# SWITCHING.net
KiCad netlist of a schematic drawn in Altium Designer
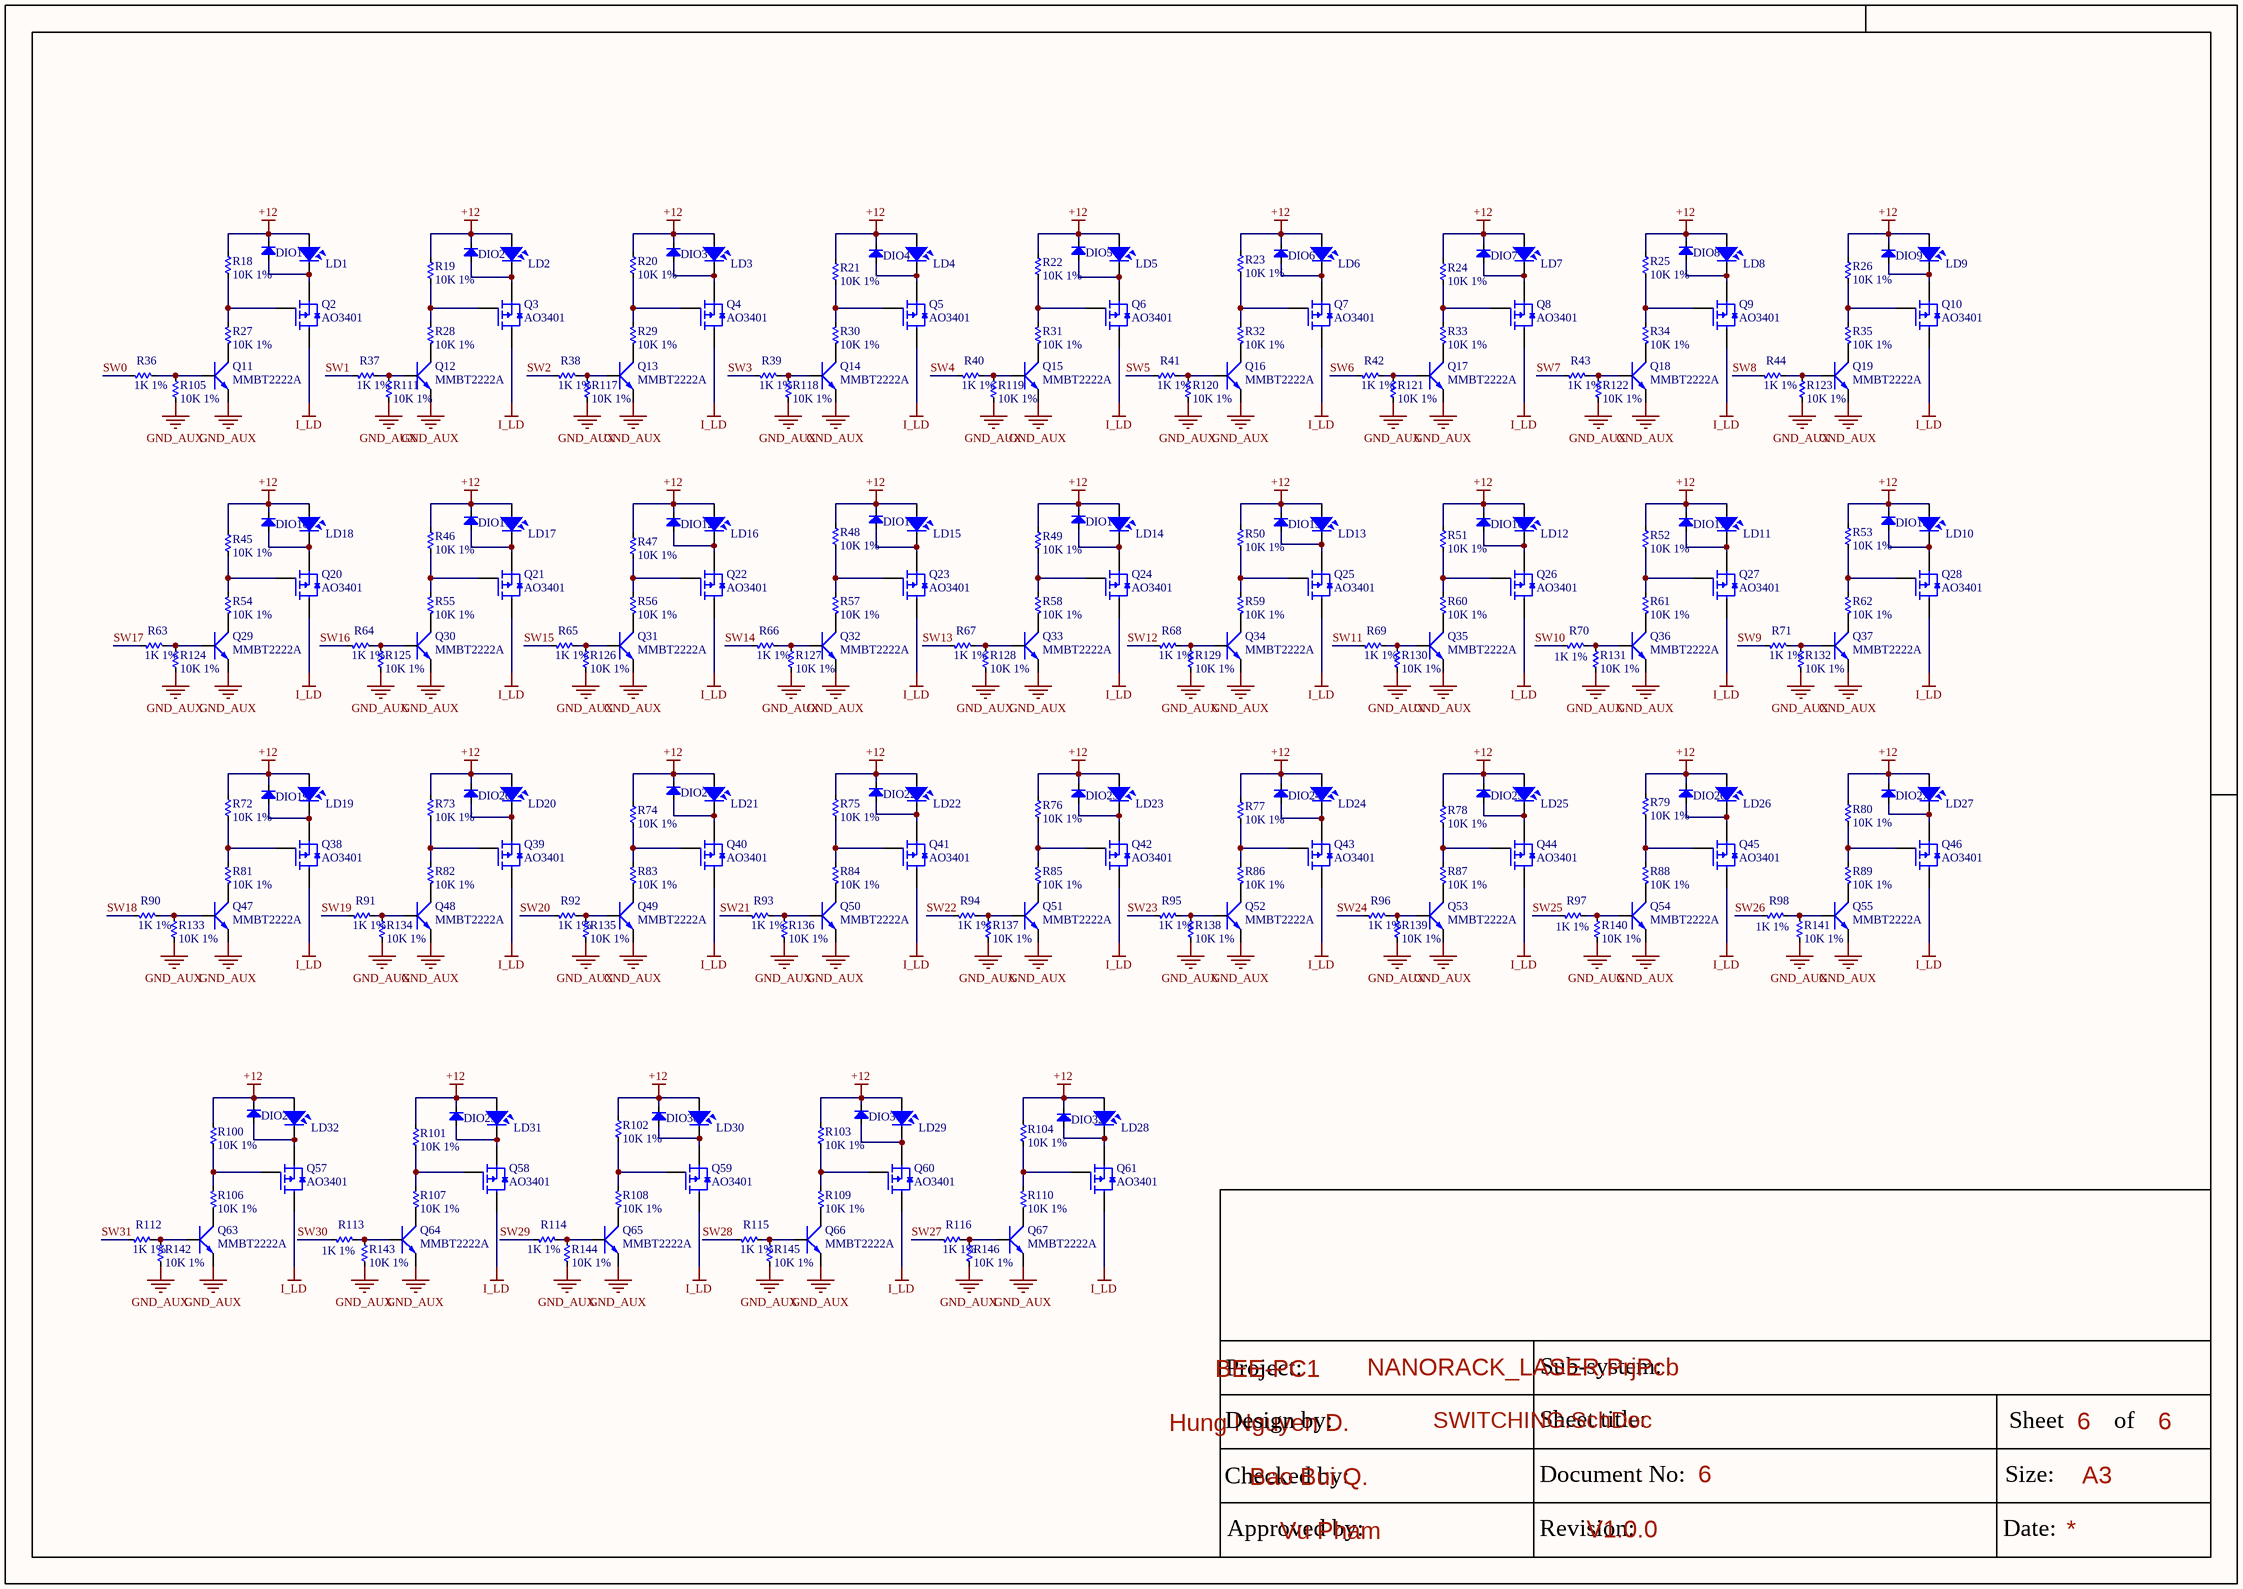
[diagram p0: SWITCHING.SchDoc]

(export (version "E")
  (design (tool "Eeschema 10.0.6"))
  (components
    (comp (ref "DIO1")
      (value "Diode SMD")
      (footprint "SOD23")
      (description "Default Diode")
      (fields (field (name "PUBLISHER") "Altium Limited"))
      (libsource (lib "Library") (part "Diode SMD"))
    )
    (comp (ref "DIO2")
      (value "Diode SMD")
      (footprint "SOD23")
      (description "Default Diode")
      (fields (field (name "PUBLISHER") "Altium Limited"))
      (libsource (lib "Library") (part "Diode SMD"))
    )
    (comp (ref "DIO3")
      (value "Diode SMD")
      (footprint "SOD23")
      (description "Default Diode")
      (fields (field (name "PUBLISHER") "Altium Limited"))
      (libsource (lib "Library") (part "Diode SMD"))
    )
    (comp (ref "DIO4")
      (value "Diode SMD")
      (footprint "SOD23")
      (description "Default Diode")
      (fields (field (name "PUBLISHER") "Altium Limited"))
      (libsource (lib "Library") (part "Diode SMD"))
    )
    (comp (ref "DIO5")
      (value "Diode SMD")
      (footprint "SOD23")
      (description "Default Diode")
      (fields (field (name "PUBLISHER") "Altium Limited"))
      (libsource (lib "Library") (part "Diode SMD"))
    )
    (comp (ref "DIO6")
      (value "Diode SMD")
      (footprint "SOD23")
      (description "Default Diode")
      (fields (field (name "PUBLISHER") "Altium Limited"))
      (libsource (lib "Library") (part "Diode SMD"))
    )
    (comp (ref "DIO7")
      (value "Diode SMD")
      (footprint "SOD23")
      (description "Default Diode")
      (fields (field (name "PUBLISHER") "Altium Limited"))
      (libsource (lib "Library") (part "Diode SMD"))
    )
    (comp (ref "DIO8")
      (value "Diode SMD")
      (footprint "SOD23")
      (description "Default Diode")
      (fields (field (name "PUBLISHER") "Altium Limited"))
      (libsource (lib "Library") (part "Diode SMD"))
    )
    (comp (ref "DIO9")
      (value "Diode SMD")
      (footprint "SOD23")
      (description "Default Diode")
      (fields (field (name "PUBLISHER") "Altium Limited"))
      (libsource (lib "Library") (part "Diode SMD"))
    )
    (comp (ref "DIO10")
      (value "Diode SMD")
      (footprint "SOD23")
      (description "Default Diode")
      (fields (field (name "PUBLISHER") "Altium Limited"))
      (libsource (lib "Library") (part "Diode SMD"))
    )
    (comp (ref "DIO11")
      (value "Diode SMD")
      (footprint "SOD23")
      (description "Default Diode")
      (fields (field (name "PUBLISHER") "Altium Limited"))
      (libsource (lib "Library") (part "Diode SMD"))
    )
    (comp (ref "DIO12")
      (value "Diode SMD")
      (footprint "SOD23")
      (description "Default Diode")
      (fields (field (name "PUBLISHER") "Altium Limited"))
      (libsource (lib "Library") (part "Diode SMD"))
    )
    (comp (ref "DIO13")
      (value "Diode SMD")
      (footprint "SOD23")
      (description "Default Diode")
      (fields (field (name "PUBLISHER") "Altium Limited"))
      (libsource (lib "Library") (part "Diode SMD"))
    )
    (comp (ref "DIO14")
      (value "Diode SMD")
      (footprint "SOD23")
      (description "Default Diode")
      (fields (field (name "PUBLISHER") "Altium Limited"))
      (libsource (lib "Library") (part "Diode SMD"))
    )
    (comp (ref "DIO15")
      (value "Diode SMD")
      (footprint "SOD23")
      (description "Default Diode")
      (fields (field (name "PUBLISHER") "Altium Limited"))
      (libsource (lib "Library") (part "Diode SMD"))
    )
    (comp (ref "DIO16")
      (value "Diode SMD")
      (footprint "SOD23")
      (description "Default Diode")
      (fields (field (name "PUBLISHER") "Altium Limited"))
      (libsource (lib "Library") (part "Diode SMD"))
    )
    (comp (ref "DIO17")
      (value "Diode SMD")
      (footprint "SOD23")
      (description "Default Diode")
      (fields (field (name "PUBLISHER") "Altium Limited"))
      (libsource (lib "Library") (part "Diode SMD"))
    )
    (comp (ref "DIO18")
      (value "Diode SMD")
      (footprint "SOD23")
      (description "Default Diode")
      (fields (field (name "PUBLISHER") "Altium Limited"))
      (libsource (lib "Library") (part "Diode SMD"))
    )
    (comp (ref "DIO19")
      (value "Diode SMD")
      (footprint "SOD23")
      (description "Default Diode")
      (fields (field (name "PUBLISHER") "Altium Limited"))
      (libsource (lib "Library") (part "Diode SMD"))
    )
    (comp (ref "DIO20")
      (value "Diode SMD")
      (footprint "SOD23")
      (description "Default Diode")
      (fields (field (name "PUBLISHER") "Altium Limited"))
      (libsource (lib "Library") (part "Diode SMD"))
    )
    (comp (ref "DIO21")
      (value "Diode SMD")
      (footprint "SOD23")
      (description "Default Diode")
      (fields (field (name "PUBLISHER") "Altium Limited"))
      (libsource (lib "Library") (part "Diode SMD"))
    )
    (comp (ref "DIO22")
      (value "Diode SMD")
      (footprint "SOD23")
      (description "Default Diode")
      (fields (field (name "PUBLISHER") "Altium Limited"))
      (libsource (lib "Library") (part "Diode SMD"))
    )
    (comp (ref "DIO23")
      (value "Diode SMD")
      (footprint "SOD23")
      (description "Default Diode")
      (fields (field (name "PUBLISHER") "Altium Limited"))
      (libsource (lib "Library") (part "Diode SMD"))
    )
    (comp (ref "DIO24")
      (value "Diode SMD")
      (footprint "SOD23")
      (description "Default Diode")
      (fields (field (name "PUBLISHER") "Altium Limited"))
      (libsource (lib "Library") (part "Diode SMD"))
    )
    (comp (ref "DIO25")
      (value "Diode SMD")
      (footprint "SOD23")
      (description "Default Diode")
      (fields (field (name "PUBLISHER") "Altium Limited"))
      (libsource (lib "Library") (part "Diode SMD"))
    )
    (comp (ref "DIO26")
      (value "Diode SMD")
      (footprint "SOD23")
      (description "Default Diode")
      (fields (field (name "PUBLISHER") "Altium Limited"))
      (libsource (lib "Library") (part "Diode SMD"))
    )
    (comp (ref "DIO27")
      (value "Diode SMD")
      (footprint "SOD23")
      (description "Default Diode")
      (fields (field (name "PUBLISHER") "Altium Limited"))
      (libsource (lib "Library") (part "Diode SMD"))
    )
    (comp (ref "DIO28")
      (value "Diode SMD")
      (footprint "SOD23")
      (description "Default Diode")
      (fields (field (name "PUBLISHER") "Altium Limited"))
      (libsource (lib "Library") (part "Diode SMD"))
    )
    (comp (ref "DIO29")
      (value "Diode SMD")
      (footprint "SOD23")
      (description "Default Diode")
      (fields (field (name "PUBLISHER") "Altium Limited"))
      (libsource (lib "Library") (part "Diode SMD"))
    )
    (comp (ref "DIO30")
      (value "Diode SMD")
      (footprint "SOD23")
      (description "Default Diode")
      (fields (field (name "PUBLISHER") "Altium Limited"))
      (libsource (lib "Library") (part "Diode SMD"))
    )
    (comp (ref "DIO31")
      (value "Diode SMD")
      (footprint "SOD23")
      (description "Default Diode")
      (fields (field (name "PUBLISHER") "Altium Limited"))
      (libsource (lib "Library") (part "Diode SMD"))
    )
    (comp (ref "DIO32")
      (value "Diode SMD")
      (footprint "SOD23")
      (description "Default Diode")
      (fields (field (name "PUBLISHER") "Altium Limited"))
      (libsource (lib "Library") (part "Diode SMD"))
    )
    (comp (ref "LD1") (value "LaserDiode") (footprint "LASER") (libsource (lib "Library") (part "LD")))
    (comp (ref "LD2") (value "LaserDiode") (footprint "LASER") (libsource (lib "Library") (part "LD")))
    (comp (ref "LD3") (value "LaserDiode") (footprint "LASER") (libsource (lib "Library") (part "LD")))
    (comp (ref "LD4") (value "LaserDiode") (footprint "LASER") (libsource (lib "Library") (part "LD")))
    (comp (ref "LD5") (value "LaserDiode") (footprint "LASER") (libsource (lib "Library") (part "LD")))
    (comp (ref "LD6") (value "LaserDiode") (footprint "LASER") (libsource (lib "Library") (part "LD")))
    (comp (ref "LD7") (value "LaserDiode") (footprint "LASER") (libsource (lib "Library") (part "LD")))
    (comp (ref "LD8") (value "LaserDiode") (footprint "LASER") (libsource (lib "Library") (part "LD")))
    (comp (ref "LD9") (value "LaserDiode") (footprint "LASER") (libsource (lib "Library") (part "LD")))
    (comp (ref "LD10") (value "LaserDiode") (footprint "LASER") (libsource (lib "Library") (part "LD")))
    (comp (ref "LD11") (value "LaserDiode") (footprint "LASER") (libsource (lib "Library") (part "LD")))
    (comp (ref "LD12") (value "LaserDiode") (footprint "LASER") (libsource (lib "Library") (part "LD")))
    (comp (ref "LD13") (value "LaserDiode") (footprint "LASER") (libsource (lib "Library") (part "LD")))
    (comp (ref "LD14") (value "LaserDiode") (footprint "LASER") (libsource (lib "Library") (part "LD")))
    (comp (ref "LD15") (value "LaserDiode") (footprint "LASER") (libsource (lib "Library") (part "LD")))
    (comp (ref "LD16") (value "LaserDiode") (footprint "LASER") (libsource (lib "Library") (part "LD")))
    (comp (ref "LD17") (value "LaserDiode") (footprint "LASER") (libsource (lib "Library") (part "LD")))
    (comp (ref "LD18") (value "LaserDiode") (footprint "LASER") (libsource (lib "Library") (part "LD")))
    (comp (ref "LD19") (value "LaserDiode") (footprint "LASER") (libsource (lib "Library") (part "LD")))
    (comp (ref "LD20") (value "LaserDiode") (footprint "LASER") (libsource (lib "Library") (part "LD")))
    (comp (ref "LD21") (value "LaserDiode") (footprint "LASER") (libsource (lib "Library") (part "LD")))
    (comp (ref "LD22") (value "LaserDiode") (footprint "LASER") (libsource (lib "Library") (part "LD")))
    (comp (ref "LD23") (value "LaserDiode") (footprint "LASER") (libsource (lib "Library") (part "LD")))
    (comp (ref "LD24") (value "LaserDiode") (footprint "LASER") (libsource (lib "Library") (part "LD")))
    (comp (ref "LD25") (value "LaserDiode") (footprint "LASER") (libsource (lib "Library") (part "LD")))
    (comp (ref "LD26") (value "LaserDiode") (footprint "LASER") (libsource (lib "Library") (part "LD")))
    (comp (ref "LD27") (value "LaserDiode") (footprint "LASER") (libsource (lib "Library") (part "LD")))
    (comp (ref "LD28") (value "LaserDiode") (footprint "LASER") (libsource (lib "Library") (part "LD")))
    (comp (ref "LD29") (value "LaserDiode") (footprint "LASER") (libsource (lib "Library") (part "LD")))
    (comp (ref "LD30") (value "LaserDiode") (footprint "LASER") (libsource (lib "Library") (part "LD")))
    (comp (ref "LD31") (value "LaserDiode") (footprint "LASER") (libsource (lib "Library") (part "LD")))
    (comp (ref "LD32") (value "LaserDiode") (footprint "LASER") (libsource (lib "Library") (part "LD")))
    (comp (ref "Q2") (value "AO3401") (footprint "SOT23-123") (libsource (lib "Library") (part "FET-P")))
    (comp (ref "Q3") (value "AO3401") (footprint "SOT23-123") (libsource (lib "Library") (part "FET-P")))
    (comp (ref "Q4") (value "AO3401") (footprint "SOT23-123") (libsource (lib "Library") (part "FET-P")))
    (comp (ref "Q5") (value "AO3401") (footprint "SOT23-123") (libsource (lib "Library") (part "FET-P")))
    (comp (ref "Q6") (value "AO3401") (footprint "SOT23-123") (libsource (lib "Library") (part "FET-P")))
    (comp (ref "Q7") (value "AO3401") (footprint "SOT23-123") (libsource (lib "Library") (part "FET-P")))
    (comp (ref "Q8") (value "AO3401") (footprint "SOT23-123") (libsource (lib "Library") (part "FET-P")))
    (comp (ref "Q9") (value "AO3401") (footprint "SOT23-123") (libsource (lib "Library") (part "FET-P")))
    (comp (ref "Q10") (value "AO3401") (footprint "SOT23-123") (libsource (lib "Library") (part "FET-P")))
    (comp (ref "Q11")
      (value "MMBT2222A")
      (footprint "SOT23-132")
      (description "SOT23-3")
      (libsource (lib "Library") (part "2SC1815"))
    )
    (comp (ref "Q12")
      (value "MMBT2222A")
      (footprint "SOT23-132")
      (description "SOT23-3")
      (libsource (lib "Library") (part "2SC1815"))
    )
    (comp (ref "Q13")
      (value "MMBT2222A")
      (footprint "SOT23-132")
      (description "SOT23-3")
      (libsource (lib "Library") (part "2SC1815"))
    )
    (comp (ref "Q14")
      (value "MMBT2222A")
      (footprint "SOT23-132")
      (description "SOT23-3")
      (libsource (lib "Library") (part "2SC1815"))
    )
    (comp (ref "Q15")
      (value "MMBT2222A")
      (footprint "SOT23-132")
      (description "SOT23-3")
      (libsource (lib "Library") (part "2SC1815"))
    )
    (comp (ref "Q16")
      (value "MMBT2222A")
      (footprint "SOT23-132")
      (description "SOT23-3")
      (libsource (lib "Library") (part "2SC1815"))
    )
    (comp (ref "Q17")
      (value "MMBT2222A")
      (footprint "SOT23-132")
      (description "SOT23-3")
      (libsource (lib "Library") (part "2SC1815"))
    )
    (comp (ref "Q18")
      (value "MMBT2222A")
      (footprint "SOT23-132")
      (description "SOT23-3")
      (libsource (lib "Library") (part "2SC1815"))
    )
    (comp (ref "Q19")
      (value "MMBT2222A")
      (footprint "SOT23-132")
      (description "SOT23-3")
      (libsource (lib "Library") (part "2SC1815"))
    )
    (comp (ref "Q20") (value "AO3401") (footprint "SOT23-123") (libsource (lib "Library") (part "FET-P")))
    (comp (ref "Q21") (value "AO3401") (footprint "SOT23-123") (libsource (lib "Library") (part "FET-P")))
    (comp (ref "Q22") (value "AO3401") (footprint "SOT23-123") (libsource (lib "Library") (part "FET-P")))
    (comp (ref "Q23") (value "AO3401") (footprint "SOT23-123") (libsource (lib "Library") (part "FET-P")))
    (comp (ref "Q24") (value "AO3401") (footprint "SOT23-123") (libsource (lib "Library") (part "FET-P")))
    (comp (ref "Q25") (value "AO3401") (footprint "SOT23-123") (libsource (lib "Library") (part "FET-P")))
    (comp (ref "Q26") (value "AO3401") (footprint "SOT23-123") (libsource (lib "Library") (part "FET-P")))
    (comp (ref "Q27") (value "AO3401") (footprint "SOT23-123") (libsource (lib "Library") (part "FET-P")))
    (comp (ref "Q28") (value "AO3401") (footprint "SOT23-123") (libsource (lib "Library") (part "FET-P")))
    (comp (ref "Q29")
      (value "MMBT2222A")
      (footprint "SOT23-132")
      (description "SOT23-3")
      (libsource (lib "Library") (part "2SC1815"))
    )
    (comp (ref "Q30")
      (value "MMBT2222A")
      (footprint "SOT23-132")
      (description "SOT23-3")
      (libsource (lib "Library") (part "2SC1815"))
    )
    (comp (ref "Q31")
      (value "MMBT2222A")
      (footprint "SOT23-132")
      (description "SOT23-3")
      (libsource (lib "Library") (part "2SC1815"))
    )
    (comp (ref "Q32")
      (value "MMBT2222A")
      (footprint "SOT23-132")
      (description "SOT23-3")
      (libsource (lib "Library") (part "2SC1815"))
    )
    (comp (ref "Q33")
      (value "MMBT2222A")
      (footprint "SOT23-132")
      (description "SOT23-3")
      (libsource (lib "Library") (part "2SC1815"))
    )
    (comp (ref "Q34")
      (value "MMBT2222A")
      (footprint "SOT23-132")
      (description "SOT23-3")
      (libsource (lib "Library") (part "2SC1815"))
    )
    (comp (ref "Q35")
      (value "MMBT2222A")
      (footprint "SOT23-132")
      (description "SOT23-3")
      (libsource (lib "Library") (part "2SC1815"))
    )
    (comp (ref "Q36")
      (value "MMBT2222A")
      (footprint "SOT23-132")
      (description "SOT23-3")
      (libsource (lib "Library") (part "2SC1815"))
    )
    (comp (ref "Q37")
      (value "MMBT2222A")
      (footprint "SOT23-132")
      (description "SOT23-3")
      (libsource (lib "Library") (part "2SC1815"))
    )
    (comp (ref "Q38") (value "AO3401") (footprint "SOT23-123") (libsource (lib "Library") (part "FET-P")))
    (comp (ref "Q39") (value "AO3401") (footprint "SOT23-123") (libsource (lib "Library") (part "FET-P")))
    (comp (ref "Q40") (value "AO3401") (footprint "SOT23-123") (libsource (lib "Library") (part "FET-P")))
    (comp (ref "Q41") (value "AO3401") (footprint "SOT23-123") (libsource (lib "Library") (part "FET-P")))
    (comp (ref "Q42") (value "AO3401") (footprint "SOT23-123") (libsource (lib "Library") (part "FET-P")))
    (comp (ref "Q43") (value "AO3401") (footprint "SOT23-123") (libsource (lib "Library") (part "FET-P")))
    (comp (ref "Q44") (value "AO3401") (footprint "SOT23-123") (libsource (lib "Library") (part "FET-P")))
    (comp (ref "Q45") (value "AO3401") (footprint "SOT23-123") (libsource (lib "Library") (part "FET-P")))
    (comp (ref "Q46") (value "AO3401") (footprint "SOT23-123") (libsource (lib "Library") (part "FET-P")))
    (comp (ref "Q47")
      (value "MMBT2222A")
      (footprint "SOT23-132")
      (description "SOT23-3")
      (libsource (lib "Library") (part "2SC1815"))
    )
    (comp (ref "Q48")
      (value "MMBT2222A")
      (footprint "SOT23-132")
      (description "SOT23-3")
      (libsource (lib "Library") (part "2SC1815"))
    )
    (comp (ref "Q49")
      (value "MMBT2222A")
      (footprint "SOT23-132")
      (description "SOT23-3")
      (libsource (lib "Library") (part "2SC1815"))
    )
    (comp (ref "Q50")
      (value "MMBT2222A")
      (footprint "SOT23-132")
      (description "SOT23-3")
      (libsource (lib "Library") (part "2SC1815"))
    )
    (comp (ref "Q51")
      (value "MMBT2222A")
      (footprint "SOT23-132")
      (description "SOT23-3")
      (libsource (lib "Library") (part "2SC1815"))
    )
    (comp (ref "Q52")
      (value "MMBT2222A")
      (footprint "SOT23-132")
      (description "SOT23-3")
      (libsource (lib "Library") (part "2SC1815"))
    )
    (comp (ref "Q53")
      (value "MMBT2222A")
      (footprint "SOT23-132")
      (description "SOT23-3")
      (libsource (lib "Library") (part "2SC1815"))
    )
    (comp (ref "Q54")
      (value "MMBT2222A")
      (footprint "SOT23-132")
      (description "SOT23-3")
      (libsource (lib "Library") (part "2SC1815"))
    )
    (comp (ref "Q55")
      (value "MMBT2222A")
      (footprint "SOT23-132")
      (description "SOT23-3")
      (libsource (lib "Library") (part "2SC1815"))
    )
    (comp (ref "Q57") (value "AO3401") (footprint "SOT23-123") (libsource (lib "Library") (part "FET-P")))
    (comp (ref "Q58") (value "AO3401") (footprint "SOT23-123") (libsource (lib "Library") (part "FET-P")))
    (comp (ref "Q59") (value "AO3401") (footprint "SOT23-123") (libsource (lib "Library") (part "FET-P")))
    (comp (ref "Q60") (value "AO3401") (footprint "SOT23-123") (libsource (lib "Library") (part "FET-P")))
    (comp (ref "Q61") (value "AO3401") (footprint "SOT23-123") (libsource (lib "Library") (part "FET-P")))
    (comp (ref "Q63")
      (value "MMBT2222A")
      (footprint "SOT23-132")
      (description "SOT23-3")
      (libsource (lib "Library") (part "2SC1815"))
    )
    (comp (ref "Q64")
      (value "MMBT2222A")
      (footprint "SOT23-132")
      (description "SOT23-3")
      (libsource (lib "Library") (part "2SC1815"))
    )
    (comp (ref "Q65")
      (value "MMBT2222A")
      (footprint "SOT23-132")
      (description "SOT23-3")
      (libsource (lib "Library") (part "2SC1815"))
    )
    (comp (ref "Q66")
      (value "MMBT2222A")
      (footprint "SOT23-132")
      (description "SOT23-3")
      (libsource (lib "Library") (part "2SC1815"))
    )
    (comp (ref "Q67")
      (value "MMBT2222A")
      (footprint "SOT23-132")
      (description "SOT23-3")
      (libsource (lib "Library") (part "2SC1815"))
    )
    (comp (ref "R18")
      (value "10K 1%")
      (footprint "RES-SMD-0603")
      (description "0603")
      (fields
        (field (name "MANUFACTURER") "Generic Components")
        (field (name "PUBLISHER") "Altium Hobart Technology Centre")
      )
      (libsource (lib "Library") (part "Res-SMD"))
    )
    (comp (ref "R19")
      (value "10K 1%")
      (footprint "RES-SMD-0603")
      (description "0603")
      (fields
        (field (name "MANUFACTURER") "Generic Components")
        (field (name "PUBLISHER") "Altium Hobart Technology Centre")
      )
      (libsource (lib "Library") (part "Res-SMD"))
    )
    (comp (ref "R20")
      (value "10K 1%")
      (footprint "RES-SMD-0603")
      (description "0603")
      (fields
        (field (name "MANUFACTURER") "Generic Components")
        (field (name "PUBLISHER") "Altium Hobart Technology Centre")
      )
      (libsource (lib "Library") (part "Res-SMD"))
    )
    (comp (ref "R21")
      (value "10K 1%")
      (footprint "RES-SMD-0603")
      (description "0603")
      (fields
        (field (name "MANUFACTURER") "Generic Components")
        (field (name "PUBLISHER") "Altium Hobart Technology Centre")
      )
      (libsource (lib "Library") (part "Res-SMD"))
    )
    (comp (ref "R22")
      (value "10K 1%")
      (footprint "RES-SMD-0603")
      (description "0603")
      (fields
        (field (name "MANUFACTURER") "Generic Components")
        (field (name "PUBLISHER") "Altium Hobart Technology Centre")
      )
      (libsource (lib "Library") (part "Res-SMD"))
    )
    (comp (ref "R23")
      (value "10K 1%")
      (footprint "RES-SMD-0603")
      (description "0603")
      (fields
        (field (name "MANUFACTURER") "Generic Components")
        (field (name "PUBLISHER") "Altium Hobart Technology Centre")
      )
      (libsource (lib "Library") (part "Res-SMD"))
    )
    (comp (ref "R24")
      (value "10K 1%")
      (footprint "RES-SMD-0603")
      (description "0603")
      (fields
        (field (name "MANUFACTURER") "Generic Components")
        (field (name "PUBLISHER") "Altium Hobart Technology Centre")
      )
      (libsource (lib "Library") (part "Res-SMD"))
    )
    (comp (ref "R25")
      (value "10K 1%")
      (footprint "RES-SMD-0603")
      (description "0603")
      (fields
        (field (name "MANUFACTURER") "Generic Components")
        (field (name "PUBLISHER") "Altium Hobart Technology Centre")
      )
      (libsource (lib "Library") (part "Res-SMD"))
    )
    (comp (ref "R26")
      (value "10K 1%")
      (footprint "RES-SMD-0603")
      (description "0603")
      (fields
        (field (name "MANUFACTURER") "Generic Components")
        (field (name "PUBLISHER") "Altium Hobart Technology Centre")
      )
      (libsource (lib "Library") (part "Res-SMD"))
    )
    (comp (ref "R27")
      (value "10K 1%")
      (footprint "RES-SMD-0603")
      (description "0603")
      (fields
        (field (name "MANUFACTURER") "Generic Components")
        (field (name "PUBLISHER") "Altium Hobart Technology Centre")
      )
      (libsource (lib "Library") (part "Res-SMD"))
    )
    (comp (ref "R28")
      (value "10K 1%")
      (footprint "RES-SMD-0603")
      (description "0603")
      (fields
        (field (name "MANUFACTURER") "Generic Components")
        (field (name "PUBLISHER") "Altium Hobart Technology Centre")
      )
      (libsource (lib "Library") (part "Res-SMD"))
    )
    (comp (ref "R29")
      (value "10K 1%")
      (footprint "RES-SMD-0603")
      (description "0603")
      (fields
        (field (name "MANUFACTURER") "Generic Components")
        (field (name "PUBLISHER") "Altium Hobart Technology Centre")
      )
      (libsource (lib "Library") (part "Res-SMD"))
    )
    (comp (ref "R30")
      (value "10K 1%")
      (footprint "RES-SMD-0603")
      (description "0603")
      (fields
        (field (name "MANUFACTURER") "Generic Components")
        (field (name "PUBLISHER") "Altium Hobart Technology Centre")
      )
      (libsource (lib "Library") (part "Res-SMD"))
    )
    (comp (ref "R31")
      (value "10K 1%")
      (footprint "RES-SMD-0603")
      (description "0603")
      (fields
        (field (name "MANUFACTURER") "Generic Components")
        (field (name "PUBLISHER") "Altium Hobart Technology Centre")
      )
      (libsource (lib "Library") (part "Res-SMD"))
    )
    (comp (ref "R32")
      (value "10K 1%")
      (footprint "RES-SMD-0603")
      (description "0603")
      (fields
        (field (name "MANUFACTURER") "Generic Components")
        (field (name "PUBLISHER") "Altium Hobart Technology Centre")
      )
      (libsource (lib "Library") (part "Res-SMD"))
    )
    (comp (ref "R33")
      (value "10K 1%")
      (footprint "RES-SMD-0603")
      (description "0603")
      (fields
        (field (name "MANUFACTURER") "Generic Components")
        (field (name "PUBLISHER") "Altium Hobart Technology Centre")
      )
      (libsource (lib "Library") (part "Res-SMD"))
    )
    (comp (ref "R34")
      (value "10K 1%")
      (footprint "RES-SMD-0603")
      (description "0603")
      (fields
        (field (name "MANUFACTURER") "Generic Components")
        (field (name "PUBLISHER") "Altium Hobart Technology Centre")
      )
      (libsource (lib "Library") (part "Res-SMD"))
    )
    (comp (ref "R35")
      (value "10K 1%")
      (footprint "RES-SMD-0603")
      (description "0603")
      (fields
        (field (name "MANUFACTURER") "Generic Components")
        (field (name "PUBLISHER") "Altium Hobart Technology Centre")
      )
      (libsource (lib "Library") (part "Res-SMD"))
    )
    (comp (ref "R36")
      (value "1K 1%")
      (footprint "RES-SMD-0603")
      (description "0603")
      (fields
        (field (name "MANUFACTURER") "Generic Components")
        (field (name "PUBLISHER") "Altium Hobart Technology Centre")
      )
      (libsource (lib "Library") (part "Res-SMD"))
    )
    (comp (ref "R37")
      (value "1K 1%")
      (footprint "RES-SMD-0603")
      (description "0603")
      (fields
        (field (name "MANUFACTURER") "Generic Components")
        (field (name "PUBLISHER") "Altium Hobart Technology Centre")
      )
      (libsource (lib "Library") (part "Res-SMD"))
    )
    (comp (ref "R38")
      (value "1K 1%")
      (footprint "RES-SMD-0603")
      (description "0603")
      (fields
        (field (name "MANUFACTURER") "Generic Components")
        (field (name "PUBLISHER") "Altium Hobart Technology Centre")
      )
      (libsource (lib "Library") (part "Res-SMD"))
    )
    (comp (ref "R39")
      (value "1K 1%")
      (footprint "RES-SMD-0603")
      (description "0603")
      (fields
        (field (name "MANUFACTURER") "Generic Components")
        (field (name "PUBLISHER") "Altium Hobart Technology Centre")
      )
      (libsource (lib "Library") (part "Res-SMD"))
    )
    (comp (ref "R40")
      (value "1K 1%")
      (footprint "RES-SMD-0603")
      (description "0603")
      (fields
        (field (name "MANUFACTURER") "Generic Components")
        (field (name "PUBLISHER") "Altium Hobart Technology Centre")
      )
      (libsource (lib "Library") (part "Res-SMD"))
    )
    (comp (ref "R41")
      (value "1K 1%")
      (footprint "RES-SMD-0603")
      (description "0603")
      (fields
        (field (name "MANUFACTURER") "Generic Components")
        (field (name "PUBLISHER") "Altium Hobart Technology Centre")
      )
      (libsource (lib "Library") (part "Res-SMD"))
    )
    (comp (ref "R42")
      (value "1K 1%")
      (footprint "RES-SMD-0603")
      (description "0603")
      (fields
        (field (name "MANUFACTURER") "Generic Components")
        (field (name "PUBLISHER") "Altium Hobart Technology Centre")
      )
      (libsource (lib "Library") (part "Res-SMD"))
    )
    (comp (ref "R43")
      (value "1K 1%")
      (footprint "RES-SMD-0603")
      (description "0603")
      (fields
        (field (name "MANUFACTURER") "Generic Components")
        (field (name "PUBLISHER") "Altium Hobart Technology Centre")
      )
      (libsource (lib "Library") (part "Res-SMD"))
    )
    (comp (ref "R44")
      (value "1K 1%")
      (footprint "RES-SMD-0603")
      (description "0603")
      (fields
        (field (name "MANUFACTURER") "Generic Components")
        (field (name "PUBLISHER") "Altium Hobart Technology Centre")
      )
      (libsource (lib "Library") (part "Res-SMD"))
    )
    (comp (ref "R45")
      (value "10K 1%")
      (footprint "RES-SMD-0603")
      (description "0603")
      (fields
        (field (name "MANUFACTURER") "Generic Components")
        (field (name "PUBLISHER") "Altium Hobart Technology Centre")
      )
      (libsource (lib "Library") (part "Res-SMD"))
    )
    (comp (ref "R46")
      (value "10K 1%")
      (footprint "RES-SMD-0603")
      (description "0603")
      (fields
        (field (name "MANUFACTURER") "Generic Components")
        (field (name "PUBLISHER") "Altium Hobart Technology Centre")
      )
      (libsource (lib "Library") (part "Res-SMD"))
    )
    (comp (ref "R47")
      (value "10K 1%")
      (footprint "RES-SMD-0603")
      (description "0603")
      (fields
        (field (name "MANUFACTURER") "Generic Components")
        (field (name "PUBLISHER") "Altium Hobart Technology Centre")
      )
      (libsource (lib "Library") (part "Res-SMD"))
    )
    (comp (ref "R48")
      (value "10K 1%")
      (footprint "RES-SMD-0603")
      (description "0603")
      (fields
        (field (name "MANUFACTURER") "Generic Components")
        (field (name "PUBLISHER") "Altium Hobart Technology Centre")
      )
      (libsource (lib "Library") (part "Res-SMD"))
    )
    (comp (ref "R49")
      (value "10K 1%")
      (footprint "RES-SMD-0603")
      (description "0603")
      (fields
        (field (name "MANUFACTURER") "Generic Components")
        (field (name "PUBLISHER") "Altium Hobart Technology Centre")
      )
      (libsource (lib "Library") (part "Res-SMD"))
    )
    (comp (ref "R50")
      (value "10K 1%")
      (footprint "RES-SMD-0603")
      (description "0603")
      (fields
        (field (name "MANUFACTURER") "Generic Components")
        (field (name "PUBLISHER") "Altium Hobart Technology Centre")
      )
      (libsource (lib "Library") (part "Res-SMD"))
    )
    (comp (ref "R51")
      (value "10K 1%")
      (footprint "RES-SMD-0603")
      (description "0603")
      (fields
        (field (name "MANUFACTURER") "Generic Components")
        (field (name "PUBLISHER") "Altium Hobart Technology Centre")
      )
      (libsource (lib "Library") (part "Res-SMD"))
    )
    (comp (ref "R52")
      (value "10K 1%")
      (footprint "RES-SMD-0603")
      (description "0603")
      (fields
        (field (name "MANUFACTURER") "Generic Components")
        (field (name "PUBLISHER") "Altium Hobart Technology Centre")
      )
      (libsource (lib "Library") (part "Res-SMD"))
    )
    (comp (ref "R53")
      (value "10K 1%")
      (footprint "RES-SMD-0603")
      (description "0603")
      (fields
        (field (name "MANUFACTURER") "Generic Components")
        (field (name "PUBLISHER") "Altium Hobart Technology Centre")
      )
      (libsource (lib "Library") (part "Res-SMD"))
    )
    (comp (ref "R54")
      (value "10K 1%")
      (footprint "RES-SMD-0603")
      (description "0603")
      (fields
        (field (name "MANUFACTURER") "Generic Components")
        (field (name "PUBLISHER") "Altium Hobart Technology Centre")
      )
      (libsource (lib "Library") (part "Res-SMD"))
    )
    (comp (ref "R55")
      (value "10K 1%")
      (footprint "RES-SMD-0603")
      (description "0603")
      (fields
        (field (name "MANUFACTURER") "Generic Components")
        (field (name "PUBLISHER") "Altium Hobart Technology Centre")
      )
      (libsource (lib "Library") (part "Res-SMD"))
    )
    (comp (ref "R56")
      (value "10K 1%")
      (footprint "RES-SMD-0603")
      (description "0603")
      (fields
        (field (name "MANUFACTURER") "Generic Components")
        (field (name "PUBLISHER") "Altium Hobart Technology Centre")
      )
      (libsource (lib "Library") (part "Res-SMD"))
    )
    (comp (ref "R57")
      (value "10K 1%")
      (footprint "RES-SMD-0603")
      (description "0603")
      (fields
        (field (name "MANUFACTURER") "Generic Components")
        (field (name "PUBLISHER") "Altium Hobart Technology Centre")
      )
      (libsource (lib "Library") (part "Res-SMD"))
    )
    (comp (ref "R58")
      (value "10K 1%")
      (footprint "RES-SMD-0603")
      (description "0603")
      (fields
        (field (name "MANUFACTURER") "Generic Components")
        (field (name "PUBLISHER") "Altium Hobart Technology Centre")
      )
      (libsource (lib "Library") (part "Res-SMD"))
    )
    (comp (ref "R59")
      (value "10K 1%")
      (footprint "RES-SMD-0603")
      (description "0603")
      (fields
        (field (name "MANUFACTURER") "Generic Components")
        (field (name "PUBLISHER") "Altium Hobart Technology Centre")
      )
      (libsource (lib "Library") (part "Res-SMD"))
    )
    (comp (ref "R60")
      (value "10K 1%")
      (footprint "RES-SMD-0603")
      (description "0603")
      (fields
        (field (name "MANUFACTURER") "Generic Components")
        (field (name "PUBLISHER") "Altium Hobart Technology Centre")
      )
      (libsource (lib "Library") (part "Res-SMD"))
    )
    (comp (ref "R61")
      (value "10K 1%")
      (footprint "RES-SMD-0603")
      (description "0603")
      (fields
        (field (name "MANUFACTURER") "Generic Components")
        (field (name "PUBLISHER") "Altium Hobart Technology Centre")
      )
      (libsource (lib "Library") (part "Res-SMD"))
    )
    (comp (ref "R62")
      (value "10K 1%")
      (footprint "RES-SMD-0603")
      (description "0603")
      (fields
        (field (name "MANUFACTURER") "Generic Components")
        (field (name "PUBLISHER") "Altium Hobart Technology Centre")
      )
      (libsource (lib "Library") (part "Res-SMD"))
    )
    (comp (ref "R63")
      (value "1K 1%")
      (footprint "RES-SMD-0603")
      (description "0603")
      (fields
        (field (name "MANUFACTURER") "Generic Components")
        (field (name "PUBLISHER") "Altium Hobart Technology Centre")
      )
      (libsource (lib "Library") (part "Res-SMD"))
    )
    (comp (ref "R64")
      (value "1K 1%")
      (footprint "RES-SMD-0603")
      (description "0603")
      (fields
        (field (name "MANUFACTURER") "Generic Components")
        (field (name "PUBLISHER") "Altium Hobart Technology Centre")
      )
      (libsource (lib "Library") (part "Res-SMD"))
    )
    (comp (ref "R65")
      (value "1K 1%")
      (footprint "RES-SMD-0603")
      (description "0603")
      (fields
        (field (name "MANUFACTURER") "Generic Components")
        (field (name "PUBLISHER") "Altium Hobart Technology Centre")
      )
      (libsource (lib "Library") (part "Res-SMD"))
    )
    (comp (ref "R66")
      (value "1K 1%")
      (footprint "RES-SMD-0603")
      (description "0603")
      (fields
        (field (name "MANUFACTURER") "Generic Components")
        (field (name "PUBLISHER") "Altium Hobart Technology Centre")
      )
      (libsource (lib "Library") (part "Res-SMD"))
    )
    (comp (ref "R67")
      (value "1K 1%")
      (footprint "RES-SMD-0603")
      (description "0603")
      (fields
        (field (name "MANUFACTURER") "Generic Components")
        (field (name "PUBLISHER") "Altium Hobart Technology Centre")
      )
      (libsource (lib "Library") (part "Res-SMD"))
    )
    (comp (ref "R68")
      (value "1K 1%")
      (footprint "RES-SMD-0603")
      (description "0603")
      (fields
        (field (name "MANUFACTURER") "Generic Components")
        (field (name "PUBLISHER") "Altium Hobart Technology Centre")
      )
      (libsource (lib "Library") (part "Res-SMD"))
    )
    (comp (ref "R69")
      (value "1K 1%")
      (footprint "RES-SMD-0603")
      (description "0603")
      (fields
        (field (name "MANUFACTURER") "Generic Components")
        (field (name "PUBLISHER") "Altium Hobart Technology Centre")
      )
      (libsource (lib "Library") (part "Res-SMD"))
    )
    (comp (ref "R70")
      (value "1K 1%")
      (footprint "RES-SMD-0603")
      (description "0603")
      (fields
        (field (name "MANUFACTURER") "Generic Components")
        (field (name "PUBLISHER") "Altium Hobart Technology Centre")
      )
      (libsource (lib "Library") (part "Res-SMD"))
    )
    (comp (ref "R71")
      (value "1K 1%")
      (footprint "RES-SMD-0603")
      (description "0603")
      (fields
        (field (name "MANUFACTURER") "Generic Components")
        (field (name "PUBLISHER") "Altium Hobart Technology Centre")
      )
      (libsource (lib "Library") (part "Res-SMD"))
    )
    (comp (ref "R72")
      (value "10K 1%")
      (footprint "RES-SMD-0603")
      (description "0603")
      (fields
        (field (name "MANUFACTURER") "Generic Components")
        (field (name "PUBLISHER") "Altium Hobart Technology Centre")
      )
      (libsource (lib "Library") (part "Res-SMD"))
    )
    (comp (ref "R73")
      (value "10K 1%")
      (footprint "RES-SMD-0603")
      (description "0603")
      (fields
        (field (name "MANUFACTURER") "Generic Components")
        (field (name "PUBLISHER") "Altium Hobart Technology Centre")
      )
      (libsource (lib "Library") (part "Res-SMD"))
    )
    (comp (ref "R74")
      (value "10K 1%")
      (footprint "RES-SMD-0603")
      (description "0603")
      (fields
        (field (name "MANUFACTURER") "Generic Components")
        (field (name "PUBLISHER") "Altium Hobart Technology Centre")
      )
      (libsource (lib "Library") (part "Res-SMD"))
    )
    (comp (ref "R75")
      (value "10K 1%")
      (footprint "RES-SMD-0603")
      (description "0603")
      (fields
        (field (name "MANUFACTURER") "Generic Components")
        (field (name "PUBLISHER") "Altium Hobart Technology Centre")
      )
      (libsource (lib "Library") (part "Res-SMD"))
    )
    (comp (ref "R76")
      (value "10K 1%")
      (footprint "RES-SMD-0603")
      (description "0603")
      (fields
        (field (name "MANUFACTURER") "Generic Components")
        (field (name "PUBLISHER") "Altium Hobart Technology Centre")
      )
      (libsource (lib "Library") (part "Res-SMD"))
    )
    (comp (ref "R77")
      (value "10K 1%")
      (footprint "RES-SMD-0603")
      (description "0603")
      (fields
        (field (name "MANUFACTURER") "Generic Components")
        (field (name "PUBLISHER") "Altium Hobart Technology Centre")
      )
      (libsource (lib "Library") (part "Res-SMD"))
    )
    (comp (ref "R78")
      (value "10K 1%")
      (footprint "RES-SMD-0603")
      (description "0603")
      (fields
        (field (name "MANUFACTURER") "Generic Components")
        (field (name "PUBLISHER") "Altium Hobart Technology Centre")
      )
      (libsource (lib "Library") (part "Res-SMD"))
    )
    (comp (ref "R79")
      (value "10K 1%")
      (footprint "RES-SMD-0603")
      (description "0603")
      (fields
        (field (name "MANUFACTURER") "Generic Components")
        (field (name "PUBLISHER") "Altium Hobart Technology Centre")
      )
      (libsource (lib "Library") (part "Res-SMD"))
    )
    (comp (ref "R80")
      (value "10K 1%")
      (footprint "RES-SMD-0603")
      (description "0603")
      (fields
        (field (name "MANUFACTURER") "Generic Components")
        (field (name "PUBLISHER") "Altium Hobart Technology Centre")
      )
      (libsource (lib "Library") (part "Res-SMD"))
    )
    (comp (ref "R81")
      (value "10K 1%")
      (footprint "RES-SMD-0603")
      (description "0603")
      (fields
        (field (name "MANUFACTURER") "Generic Components")
        (field (name "PUBLISHER") "Altium Hobart Technology Centre")
      )
      (libsource (lib "Library") (part "Res-SMD"))
    )
    (comp (ref "R82")
      (value "10K 1%")
      (footprint "RES-SMD-0603")
      (description "0603")
      (fields
        (field (name "MANUFACTURER") "Generic Components")
        (field (name "PUBLISHER") "Altium Hobart Technology Centre")
      )
      (libsource (lib "Library") (part "Res-SMD"))
    )
    (comp (ref "R83")
      (value "10K 1%")
      (footprint "RES-SMD-0603")
      (description "0603")
      (fields
        (field (name "MANUFACTURER") "Generic Components")
        (field (name "PUBLISHER") "Altium Hobart Technology Centre")
      )
      (libsource (lib "Library") (part "Res-SMD"))
    )
    (comp (ref "R84")
      (value "10K 1%")
      (footprint "RES-SMD-0603")
      (description "0603")
      (fields
        (field (name "MANUFACTURER") "Generic Components")
        (field (name "PUBLISHER") "Altium Hobart Technology Centre")
      )
      (libsource (lib "Library") (part "Res-SMD"))
    )
    (comp (ref "R85")
      (value "10K 1%")
      (footprint "RES-SMD-0603")
      (description "0603")
      (fields
        (field (name "MANUFACTURER") "Generic Components")
        (field (name "PUBLISHER") "Altium Hobart Technology Centre")
      )
      (libsource (lib "Library") (part "Res-SMD"))
    )
    (comp (ref "R86")
      (value "10K 1%")
      (footprint "RES-SMD-0603")
      (description "0603")
      (fields
        (field (name "MANUFACTURER") "Generic Components")
        (field (name "PUBLISHER") "Altium Hobart Technology Centre")
      )
      (libsource (lib "Library") (part "Res-SMD"))
    )
    (comp (ref "R87")
      (value "10K 1%")
      (footprint "RES-SMD-0603")
      (description "0603")
      (fields
        (field (name "MANUFACTURER") "Generic Components")
        (field (name "PUBLISHER") "Altium Hobart Technology Centre")
      )
      (libsource (lib "Library") (part "Res-SMD"))
    )
    (comp (ref "R88")
      (value "10K 1%")
      (footprint "RES-SMD-0603")
      (description "0603")
      (fields
        (field (name "MANUFACTURER") "Generic Components")
        (field (name "PUBLISHER") "Altium Hobart Technology Centre")
      )
      (libsource (lib "Library") (part "Res-SMD"))
    )
    (comp (ref "R89")
      (value "10K 1%")
      (footprint "RES-SMD-0603")
      (description "0603")
      (fields
        (field (name "MANUFACTURER") "Generic Components")
        (field (name "PUBLISHER") "Altium Hobart Technology Centre")
      )
      (libsource (lib "Library") (part "Res-SMD"))
    )
    (comp (ref "R90")
      (value "1K 1%")
      (footprint "RES-SMD-0603")
      (description "0603")
      (fields
        (field (name "MANUFACTURER") "Generic Components")
        (field (name "PUBLISHER") "Altium Hobart Technology Centre")
      )
      (libsource (lib "Library") (part "Res-SMD"))
    )
    (comp (ref "R91")
      (value "1K 1%")
      (footprint "RES-SMD-0603")
      (description "0603")
      (fields
        (field (name "MANUFACTURER") "Generic Components")
        (field (name "PUBLISHER") "Altium Hobart Technology Centre")
      )
      (libsource (lib "Library") (part "Res-SMD"))
    )
    (comp (ref "R92")
      (value "1K 1%")
      (footprint "RES-SMD-0603")
      (description "0603")
      (fields
        (field (name "MANUFACTURER") "Generic Components")
        (field (name "PUBLISHER") "Altium Hobart Technology Centre")
      )
      (libsource (lib "Library") (part "Res-SMD"))
    )
    (comp (ref "R93")
      (value "1K 1%")
      (footprint "RES-SMD-0603")
      (description "0603")
      (fields
        (field (name "MANUFACTURER") "Generic Components")
        (field (name "PUBLISHER") "Altium Hobart Technology Centre")
      )
      (libsource (lib "Library") (part "Res-SMD"))
    )
    (comp (ref "R94")
      (value "1K 1%")
      (footprint "RES-SMD-0603")
      (description "0603")
      (fields
        (field (name "MANUFACTURER") "Generic Components")
        (field (name "PUBLISHER") "Altium Hobart Technology Centre")
      )
      (libsource (lib "Library") (part "Res-SMD"))
    )
    (comp (ref "R95")
      (value "1K 1%")
      (footprint "RES-SMD-0603")
      (description "0603")
      (fields
        (field (name "MANUFACTURER") "Generic Components")
        (field (name "PUBLISHER") "Altium Hobart Technology Centre")
      )
      (libsource (lib "Library") (part "Res-SMD"))
    )
    (comp (ref "R96")
      (value "1K 1%")
      (footprint "RES-SMD-0603")
      (description "0603")
      (fields
        (field (name "MANUFACTURER") "Generic Components")
        (field (name "PUBLISHER") "Altium Hobart Technology Centre")
      )
      (libsource (lib "Library") (part "Res-SMD"))
    )
    (comp (ref "R97")
      (value "1K 1%")
      (footprint "RES-SMD-0603")
      (description "0603")
      (fields
        (field (name "MANUFACTURER") "Generic Components")
        (field (name "PUBLISHER") "Altium Hobart Technology Centre")
      )
      (libsource (lib "Library") (part "Res-SMD"))
    )
    (comp (ref "R98")
      (value "1K 1%")
      (footprint "RES-SMD-0603")
      (description "0603")
      (fields
        (field (name "MANUFACTURER") "Generic Components")
        (field (name "PUBLISHER") "Altium Hobart Technology Centre")
      )
      (libsource (lib "Library") (part "Res-SMD"))
    )
    (comp (ref "R100")
      (value "10K 1%")
      (footprint "RES-SMD-0603")
      (description "0603")
      (fields
        (field (name "MANUFACTURER") "Generic Components")
        (field (name "PUBLISHER") "Altium Hobart Technology Centre")
      )
      (libsource (lib "Library") (part "Res-SMD"))
    )
    (comp (ref "R101")
      (value "10K 1%")
      (footprint "RES-SMD-0603")
      (description "0603")
      (fields
        (field (name "MANUFACTURER") "Generic Components")
        (field (name "PUBLISHER") "Altium Hobart Technology Centre")
      )
      (libsource (lib "Library") (part "Res-SMD"))
    )
    (comp (ref "R102")
      (value "10K 1%")
      (footprint "RES-SMD-0603")
      (description "0603")
      (fields
        (field (name "MANUFACTURER") "Generic Components")
        (field (name "PUBLISHER") "Altium Hobart Technology Centre")
      )
      (libsource (lib "Library") (part "Res-SMD"))
    )
    (comp (ref "R103")
      (value "10K 1%")
      (footprint "RES-SMD-0603")
      (description "0603")
      (fields
        (field (name "MANUFACTURER") "Generic Components")
        (field (name "PUBLISHER") "Altium Hobart Technology Centre")
      )
      (libsource (lib "Library") (part "Res-SMD"))
    )
    (comp (ref "R104")
      (value "10K 1%")
      (footprint "RES-SMD-0603")
      (description "0603")
      (fields
        (field (name "MANUFACTURER") "Generic Components")
        (field (name "PUBLISHER") "Altium Hobart Technology Centre")
      )
      (libsource (lib "Library") (part "Res-SMD"))
    )
    (comp (ref "R105")
      (value "10K 1%")
      (footprint "RES-SMD-0603")
      (description "0603")
      (fields
        (field (name "MANUFACTURER") "Generic Components")
        (field (name "PUBLISHER") "Altium Hobart Technology Centre")
      )
      (libsource (lib "Library") (part "Res-SMD"))
    )
    (comp (ref "R106")
      (value "10K 1%")
      (footprint "RES-SMD-0603")
      (description "0603")
      (fields
        (field (name "MANUFACTURER") "Generic Components")
        (field (name "PUBLISHER") "Altium Hobart Technology Centre")
      )
      (libsource (lib "Library") (part "Res-SMD"))
    )
    (comp (ref "R107")
      (value "10K 1%")
      (footprint "RES-SMD-0603")
      (description "0603")
      (fields
        (field (name "MANUFACTURER") "Generic Components")
        (field (name "PUBLISHER") "Altium Hobart Technology Centre")
      )
      (libsource (lib "Library") (part "Res-SMD"))
    )
    (comp (ref "R108")
      (value "10K 1%")
      (footprint "RES-SMD-0603")
      (description "0603")
      (fields
        (field (name "MANUFACTURER") "Generic Components")
        (field (name "PUBLISHER") "Altium Hobart Technology Centre")
      )
      (libsource (lib "Library") (part "Res-SMD"))
    )
    (comp (ref "R109")
      (value "10K 1%")
      (footprint "RES-SMD-0603")
      (description "0603")
      (fields
        (field (name "MANUFACTURER") "Generic Components")
        (field (name "PUBLISHER") "Altium Hobart Technology Centre")
      )
      (libsource (lib "Library") (part "Res-SMD"))
    )
    (comp (ref "R110")
      (value "10K 1%")
      (footprint "RES-SMD-0603")
      (description "0603")
      (fields
        (field (name "MANUFACTURER") "Generic Components")
        (field (name "PUBLISHER") "Altium Hobart Technology Centre")
      )
      (libsource (lib "Library") (part "Res-SMD"))
    )
    (comp (ref "R111")
      (value "10K 1%")
      (footprint "RES-SMD-0603")
      (description "0603")
      (fields
        (field (name "MANUFACTURER") "Generic Components")
        (field (name "PUBLISHER") "Altium Hobart Technology Centre")
      )
      (libsource (lib "Library") (part "Res-SMD"))
    )
    (comp (ref "R112")
      (value "1K 1%")
      (footprint "RES-SMD-0603")
      (description "0603")
      (fields
        (field (name "MANUFACTURER") "Generic Components")
        (field (name "PUBLISHER") "Altium Hobart Technology Centre")
      )
      (libsource (lib "Library") (part "Res-SMD"))
    )
    (comp (ref "R113")
      (value "1K 1%")
      (footprint "RES-SMD-0603")
      (description "0603")
      (fields
        (field (name "MANUFACTURER") "Generic Components")
        (field (name "PUBLISHER") "Altium Hobart Technology Centre")
      )
      (libsource (lib "Library") (part "Res-SMD"))
    )
    (comp (ref "R114")
      (value "1K 1%")
      (footprint "RES-SMD-0603")
      (description "0603")
      (fields
        (field (name "MANUFACTURER") "Generic Components")
        (field (name "PUBLISHER") "Altium Hobart Technology Centre")
      )
      (libsource (lib "Library") (part "Res-SMD"))
    )
    (comp (ref "R115")
      (value "1K 1%")
      (footprint "RES-SMD-0603")
      (description "0603")
      (fields
        (field (name "MANUFACTURER") "Generic Components")
        (field (name "PUBLISHER") "Altium Hobart Technology Centre")
      )
      (libsource (lib "Library") (part "Res-SMD"))
    )
    (comp (ref "R116")
      (value "1K 1%")
      (footprint "RES-SMD-0603")
      (description "0603")
      (fields
        (field (name "MANUFACTURER") "Generic Components")
        (field (name "PUBLISHER") "Altium Hobart Technology Centre")
      )
      (libsource (lib "Library") (part "Res-SMD"))
    )
    (comp (ref "R117")
      (value "10K 1%")
      (footprint "RES-SMD-0603")
      (description "0603")
      (fields
        (field (name "MANUFACTURER") "Generic Components")
        (field (name "PUBLISHER") "Altium Hobart Technology Centre")
      )
      (libsource (lib "Library") (part "Res-SMD"))
    )
    (comp (ref "R118")
      (value "10K 1%")
      (footprint "RES-SMD-0603")
      (description "0603")
      (fields
        (field (name "MANUFACTURER") "Generic Components")
        (field (name "PUBLISHER") "Altium Hobart Technology Centre")
      )
      (libsource (lib "Library") (part "Res-SMD"))
    )
    (comp (ref "R119")
      (value "10K 1%")
      (footprint "RES-SMD-0603")
      (description "0603")
      (fields
        (field (name "MANUFACTURER") "Generic Components")
        (field (name "PUBLISHER") "Altium Hobart Technology Centre")
      )
      (libsource (lib "Library") (part "Res-SMD"))
    )
    (comp (ref "R120")
      (value "10K 1%")
      (footprint "RES-SMD-0603")
      (description "0603")
      (fields
        (field (name "MANUFACTURER") "Generic Components")
        (field (name "PUBLISHER") "Altium Hobart Technology Centre")
      )
      (libsource (lib "Library") (part "Res-SMD"))
    )
    (comp (ref "R121")
      (value "10K 1%")
      (footprint "RES-SMD-0603")
      (description "0603")
      (fields
        (field (name "MANUFACTURER") "Generic Components")
        (field (name "PUBLISHER") "Altium Hobart Technology Centre")
      )
      (libsource (lib "Library") (part "Res-SMD"))
    )
    (comp (ref "R122")
      (value "10K 1%")
      (footprint "RES-SMD-0603")
      (description "0603")
      (fields
        (field (name "MANUFACTURER") "Generic Components")
        (field (name "PUBLISHER") "Altium Hobart Technology Centre")
      )
      (libsource (lib "Library") (part "Res-SMD"))
    )
    (comp (ref "R123")
      (value "10K 1%")
      (footprint "RES-SMD-0603")
      (description "0603")
      (fields
        (field (name "MANUFACTURER") "Generic Components")
        (field (name "PUBLISHER") "Altium Hobart Technology Centre")
      )
      (libsource (lib "Library") (part "Res-SMD"))
    )
    (comp (ref "R124")
      (value "10K 1%")
      (footprint "RES-SMD-0603")
      (description "0603")
      (fields
        (field (name "MANUFACTURER") "Generic Components")
        (field (name "PUBLISHER") "Altium Hobart Technology Centre")
      )
      (libsource (lib "Library") (part "Res-SMD"))
    )
    (comp (ref "R125")
      (value "10K 1%")
      (footprint "RES-SMD-0603")
      (description "0603")
      (fields
        (field (name "MANUFACTURER") "Generic Components")
        (field (name "PUBLISHER") "Altium Hobart Technology Centre")
      )
      (libsource (lib "Library") (part "Res-SMD"))
    )
    (comp (ref "R126")
      (value "10K 1%")
      (footprint "RES-SMD-0603")
      (description "0603")
      (fields
        (field (name "MANUFACTURER") "Generic Components")
        (field (name "PUBLISHER") "Altium Hobart Technology Centre")
      )
      (libsource (lib "Library") (part "Res-SMD"))
    )
    (comp (ref "R127")
      (value "10K 1%")
      (footprint "RES-SMD-0603")
      (description "0603")
      (fields
        (field (name "MANUFACTURER") "Generic Components")
        (field (name "PUBLISHER") "Altium Hobart Technology Centre")
      )
      (libsource (lib "Library") (part "Res-SMD"))
    )
    (comp (ref "R128")
      (value "10K 1%")
      (footprint "RES-SMD-0603")
      (description "0603")
      (fields
        (field (name "MANUFACTURER") "Generic Components")
        (field (name "PUBLISHER") "Altium Hobart Technology Centre")
      )
      (libsource (lib "Library") (part "Res-SMD"))
    )
    (comp (ref "R129")
      (value "10K 1%")
      (footprint "RES-SMD-0603")
      (description "0603")
      (fields
        (field (name "MANUFACTURER") "Generic Components")
        (field (name "PUBLISHER") "Altium Hobart Technology Centre")
      )
      (libsource (lib "Library") (part "Res-SMD"))
    )
    (comp (ref "R130")
      (value "10K 1%")
      (footprint "RES-SMD-0603")
      (description "0603")
      (fields
        (field (name "MANUFACTURER") "Generic Components")
        (field (name "PUBLISHER") "Altium Hobart Technology Centre")
      )
      (libsource (lib "Library") (part "Res-SMD"))
    )
    (comp (ref "R131")
      (value "10K 1%")
      (footprint "RES-SMD-0603")
      (description "0603")
      (fields
        (field (name "MANUFACTURER") "Generic Components")
        (field (name "PUBLISHER") "Altium Hobart Technology Centre")
      )
      (libsource (lib "Library") (part "Res-SMD"))
    )
    (comp (ref "R132")
      (value "10K 1%")
      (footprint "RES-SMD-0603")
      (description "0603")
      (fields
        (field (name "MANUFACTURER") "Generic Components")
        (field (name "PUBLISHER") "Altium Hobart Technology Centre")
      )
      (libsource (lib "Library") (part "Res-SMD"))
    )
    (comp (ref "R133")
      (value "10K 1%")
      (footprint "RES-SMD-0603")
      (description "0603")
      (fields
        (field (name "MANUFACTURER") "Generic Components")
        (field (name "PUBLISHER") "Altium Hobart Technology Centre")
      )
      (libsource (lib "Library") (part "Res-SMD"))
    )
    (comp (ref "R134")
      (value "10K 1%")
      (footprint "RES-SMD-0603")
      (description "0603")
      (fields
        (field (name "MANUFACTURER") "Generic Components")
        (field (name "PUBLISHER") "Altium Hobart Technology Centre")
      )
      (libsource (lib "Library") (part "Res-SMD"))
    )
    (comp (ref "R135")
      (value "10K 1%")
      (footprint "RES-SMD-0603")
      (description "0603")
      (fields
        (field (name "MANUFACTURER") "Generic Components")
        (field (name "PUBLISHER") "Altium Hobart Technology Centre")
      )
      (libsource (lib "Library") (part "Res-SMD"))
    )
    (comp (ref "R136")
      (value "10K 1%")
      (footprint "RES-SMD-0603")
      (description "0603")
      (fields
        (field (name "MANUFACTURER") "Generic Components")
        (field (name "PUBLISHER") "Altium Hobart Technology Centre")
      )
      (libsource (lib "Library") (part "Res-SMD"))
    )
    (comp (ref "R137")
      (value "10K 1%")
      (footprint "RES-SMD-0603")
      (description "0603")
      (fields
        (field (name "MANUFACTURER") "Generic Components")
        (field (name "PUBLISHER") "Altium Hobart Technology Centre")
      )
      (libsource (lib "Library") (part "Res-SMD"))
    )
    (comp (ref "R138")
      (value "10K 1%")
      (footprint "RES-SMD-0603")
      (description "0603")
      (fields
        (field (name "MANUFACTURER") "Generic Components")
        (field (name "PUBLISHER") "Altium Hobart Technology Centre")
      )
      (libsource (lib "Library") (part "Res-SMD"))
    )
    (comp (ref "R139")
      (value "10K 1%")
      (footprint "RES-SMD-0603")
      (description "0603")
      (fields
        (field (name "MANUFACTURER") "Generic Components")
        (field (name "PUBLISHER") "Altium Hobart Technology Centre")
      )
      (libsource (lib "Library") (part "Res-SMD"))
    )
    (comp (ref "R140")
      (value "10K 1%")
      (footprint "RES-SMD-0603")
      (description "0603")
      (fields
        (field (name "MANUFACTURER") "Generic Components")
        (field (name "PUBLISHER") "Altium Hobart Technology Centre")
      )
      (libsource (lib "Library") (part "Res-SMD"))
    )
    (comp (ref "R141")
      (value "10K 1%")
      (footprint "RES-SMD-0603")
      (description "0603")
      (fields
        (field (name "MANUFACTURER") "Generic Components")
        (field (name "PUBLISHER") "Altium Hobart Technology Centre")
      )
      (libsource (lib "Library") (part "Res-SMD"))
    )
    (comp (ref "R142")
      (value "10K 1%")
      (footprint "RES-SMD-0603")
      (description "0603")
      (fields
        (field (name "MANUFACTURER") "Generic Components")
        (field (name "PUBLISHER") "Altium Hobart Technology Centre")
      )
      (libsource (lib "Library") (part "Res-SMD"))
    )
    (comp (ref "R143")
      (value "10K 1%")
      (footprint "RES-SMD-0603")
      (description "0603")
      (fields
        (field (name "MANUFACTURER") "Generic Components")
        (field (name "PUBLISHER") "Altium Hobart Technology Centre")
      )
      (libsource (lib "Library") (part "Res-SMD"))
    )
    (comp (ref "R144")
      (value "10K 1%")
      (footprint "RES-SMD-0603")
      (description "0603")
      (fields
        (field (name "MANUFACTURER") "Generic Components")
        (field (name "PUBLISHER") "Altium Hobart Technology Centre")
      )
      (libsource (lib "Library") (part "Res-SMD"))
    )
    (comp (ref "R145")
      (value "10K 1%")
      (footprint "RES-SMD-0603")
      (description "0603")
      (fields
        (field (name "MANUFACTURER") "Generic Components")
        (field (name "PUBLISHER") "Altium Hobart Technology Centre")
      )
      (libsource (lib "Library") (part "Res-SMD"))
    )
    (comp (ref "R146")
      (value "10K 1%")
      (footprint "RES-SMD-0603")
      (description "0603")
      (fields
        (field (name "MANUFACTURER") "Generic Components")
        (field (name "PUBLISHER") "Altium Hobart Technology Centre")
      )
      (libsource (lib "Library") (part "Res-SMD"))
    )
  )
  (nets
    (net (code "1") (name "+12") (class "Default")
      (node (ref "DIO1") (pin "2") (pinfunction "K_2") (pintype "passive"))
      (node (ref "DIO10") (pin "2") (pinfunction "K_2") (pintype "passive"))
      (node (ref "DIO11") (pin "2") (pinfunction "K_2") (pintype "passive"))
      (node (ref "DIO12") (pin "2") (pinfunction "K_2") (pintype "passive"))
      (node (ref "DIO13") (pin "2") (pinfunction "K_2") (pintype "passive"))
      (node (ref "DIO14") (pin "2") (pinfunction "K_2") (pintype "passive"))
      (node (ref "DIO15") (pin "2") (pinfunction "K_2") (pintype "passive"))
      (node (ref "DIO16") (pin "2") (pinfunction "K_2") (pintype "passive"))
      (node (ref "DIO17") (pin "2") (pinfunction "K_2") (pintype "passive"))
      (node (ref "DIO18") (pin "2") (pinfunction "K_2") (pintype "passive"))
      (node (ref "DIO19") (pin "2") (pinfunction "K_2") (pintype "passive"))
      (node (ref "DIO2") (pin "2") (pinfunction "K_2") (pintype "passive"))
      (node (ref "DIO20") (pin "2") (pinfunction "K_2") (pintype "passive"))
      (node (ref "DIO21") (pin "2") (pinfunction "K_2") (pintype "passive"))
      (node (ref "DIO22") (pin "2") (pinfunction "K_2") (pintype "passive"))
      (node (ref "DIO23") (pin "2") (pinfunction "K_2") (pintype "passive"))
      (node (ref "DIO24") (pin "2") (pinfunction "K_2") (pintype "passive"))
      (node (ref "DIO25") (pin "2") (pinfunction "K_2") (pintype "passive"))
      (node (ref "DIO26") (pin "2") (pinfunction "K_2") (pintype "passive"))
      (node (ref "DIO27") (pin "2") (pinfunction "K_2") (pintype "passive"))
      (node (ref "DIO28") (pin "2") (pinfunction "K_2") (pintype "passive"))
      (node (ref "DIO29") (pin "2") (pinfunction "K_2") (pintype "passive"))
      (node (ref "DIO3") (pin "2") (pinfunction "K_2") (pintype "passive"))
      (node (ref "DIO30") (pin "2") (pinfunction "K_2") (pintype "passive"))
      (node (ref "DIO31") (pin "2") (pinfunction "K_2") (pintype "passive"))
      (node (ref "DIO32") (pin "2") (pinfunction "K_2") (pintype "passive"))
      (node (ref "DIO4") (pin "2") (pinfunction "K_2") (pintype "passive"))
      (node (ref "DIO5") (pin "2") (pinfunction "K_2") (pintype "passive"))
      (node (ref "DIO6") (pin "2") (pinfunction "K_2") (pintype "passive"))
      (node (ref "DIO7") (pin "2") (pinfunction "K_2") (pintype "passive"))
      (node (ref "DIO8") (pin "2") (pinfunction "K_2") (pintype "passive"))
      (node (ref "DIO9") (pin "2") (pinfunction "K_2") (pintype "passive"))
      (node (ref "LD1") (pin "1") (pinfunction "1_1") (pintype "passive"))
      (node (ref "LD10") (pin "1") (pinfunction "1_1") (pintype "passive"))
      (node (ref "LD11") (pin "1") (pinfunction "1_1") (pintype "passive"))
      (node (ref "LD12") (pin "1") (pinfunction "1_1") (pintype "passive"))
      (node (ref "LD13") (pin "1") (pinfunction "1_1") (pintype "passive"))
      (node (ref "LD14") (pin "1") (pinfunction "1_1") (pintype "passive"))
      (node (ref "LD15") (pin "1") (pinfunction "1_1") (pintype "passive"))
      (node (ref "LD16") (pin "1") (pinfunction "1_1") (pintype "passive"))
      (node (ref "LD17") (pin "1") (pinfunction "1_1") (pintype "passive"))
      (node (ref "LD18") (pin "1") (pinfunction "1_1") (pintype "passive"))
      (node (ref "LD19") (pin "1") (pinfunction "1_1") (pintype "passive"))
      (node (ref "LD2") (pin "1") (pinfunction "1_1") (pintype "passive"))
      (node (ref "LD20") (pin "1") (pinfunction "1_1") (pintype "passive"))
      (node (ref "LD21") (pin "1") (pinfunction "1_1") (pintype "passive"))
      (node (ref "LD22") (pin "1") (pinfunction "1_1") (pintype "passive"))
      (node (ref "LD23") (pin "1") (pinfunction "1_1") (pintype "passive"))
      (node (ref "LD24") (pin "1") (pinfunction "1_1") (pintype "passive"))
      (node (ref "LD25") (pin "1") (pinfunction "1_1") (pintype "passive"))
      (node (ref "LD26") (pin "1") (pinfunction "1_1") (pintype "passive"))
      (node (ref "LD27") (pin "1") (pinfunction "1_1") (pintype "passive"))
      (node (ref "LD28") (pin "1") (pinfunction "1_1") (pintype "passive"))
      (node (ref "LD29") (pin "1") (pinfunction "1_1") (pintype "passive"))
      (node (ref "LD3") (pin "1") (pinfunction "1_1") (pintype "passive"))
      (node (ref "LD30") (pin "1") (pinfunction "1_1") (pintype "passive"))
      (node (ref "LD31") (pin "1") (pinfunction "1_1") (pintype "passive"))
      (node (ref "LD32") (pin "1") (pinfunction "1_1") (pintype "passive"))
      (node (ref "LD4") (pin "1") (pinfunction "1_1") (pintype "passive"))
      (node (ref "LD5") (pin "1") (pinfunction "1_1") (pintype "passive"))
      (node (ref "LD6") (pin "1") (pinfunction "1_1") (pintype "passive"))
      (node (ref "LD7") (pin "1") (pinfunction "1_1") (pintype "passive"))
      (node (ref "LD8") (pin "1") (pinfunction "1_1") (pintype "passive"))
      (node (ref "LD9") (pin "1") (pinfunction "1_1") (pintype "passive"))
      (node (ref "R100") (pin "1") (pinfunction "1_1") (pintype "passive"))
      (node (ref "R101") (pin "1") (pinfunction "1_1") (pintype "passive"))
      (node (ref "R102") (pin "1") (pinfunction "1_1") (pintype "passive"))
      (node (ref "R103") (pin "1") (pinfunction "1_1") (pintype "passive"))
      (node (ref "R104") (pin "1") (pinfunction "1_1") (pintype "passive"))
      (node (ref "R18") (pin "1") (pinfunction "1_1") (pintype "passive"))
      (node (ref "R19") (pin "1") (pinfunction "1_1") (pintype "passive"))
      (node (ref "R20") (pin "1") (pinfunction "1_1") (pintype "passive"))
      (node (ref "R21") (pin "1") (pinfunction "1_1") (pintype "passive"))
      (node (ref "R22") (pin "1") (pinfunction "1_1") (pintype "passive"))
      (node (ref "R23") (pin "1") (pinfunction "1_1") (pintype "passive"))
      (node (ref "R24") (pin "1") (pinfunction "1_1") (pintype "passive"))
      (node (ref "R25") (pin "1") (pinfunction "1_1") (pintype "passive"))
      (node (ref "R26") (pin "1") (pinfunction "1_1") (pintype "passive"))
      (node (ref "R45") (pin "1") (pinfunction "1_1") (pintype "passive"))
      (node (ref "R46") (pin "1") (pinfunction "1_1") (pintype "passive"))
      (node (ref "R47") (pin "1") (pinfunction "1_1") (pintype "passive"))
      (node (ref "R48") (pin "1") (pinfunction "1_1") (pintype "passive"))
      (node (ref "R49") (pin "1") (pinfunction "1_1") (pintype "passive"))
      (node (ref "R50") (pin "1") (pinfunction "1_1") (pintype "passive"))
      (node (ref "R51") (pin "1") (pinfunction "1_1") (pintype "passive"))
      (node (ref "R52") (pin "1") (pinfunction "1_1") (pintype "passive"))
      (node (ref "R53") (pin "1") (pinfunction "1_1") (pintype "passive"))
      (node (ref "R72") (pin "1") (pinfunction "1_1") (pintype "passive"))
      (node (ref "R73") (pin "1") (pinfunction "1_1") (pintype "passive"))
      (node (ref "R74") (pin "1") (pinfunction "1_1") (pintype "passive"))
      (node (ref "R75") (pin "1") (pinfunction "1_1") (pintype "passive"))
      (node (ref "R76") (pin "1") (pinfunction "1_1") (pintype "passive"))
      (node (ref "R77") (pin "1") (pinfunction "1_1") (pintype "passive"))
      (node (ref "R78") (pin "1") (pinfunction "1_1") (pintype "passive"))
      (node (ref "R79") (pin "1") (pinfunction "1_1") (pintype "passive"))
      (node (ref "R80") (pin "1") (pinfunction "1_1") (pintype "passive"))
    )
    (net (code "2") (name "/SW0") (class "Default")
      (node (ref "R36") (pin "1") (pinfunction "1_1") (pintype "passive"))
    )
    (net (code "3") (name "/SW1") (class "Default")
      (node (ref "R37") (pin "1") (pinfunction "1_1") (pintype "passive"))
    )
    (net (code "4") (name "/SW2") (class "Default")
      (node (ref "R38") (pin "1") (pinfunction "1_1") (pintype "passive"))
    )
    (net (code "5") (name "/SW3") (class "Default")
      (node (ref "R39") (pin "1") (pinfunction "1_1") (pintype "passive"))
    )
    (net (code "6") (name "/SW4") (class "Default")
      (node (ref "R40") (pin "1") (pinfunction "1_1") (pintype "passive"))
    )
    (net (code "7") (name "/SW5") (class "Default")
      (node (ref "R41") (pin "1") (pinfunction "1_1") (pintype "passive"))
    )
    (net (code "8") (name "/SW6") (class "Default")
      (node (ref "R42") (pin "1") (pinfunction "1_1") (pintype "passive"))
    )
    (net (code "9") (name "/SW7") (class "Default")
      (node (ref "R43") (pin "1") (pinfunction "1_1") (pintype "passive"))
    )
    (net (code "10") (name "/SW8") (class "Default")
      (node (ref "R44") (pin "1") (pinfunction "1_1") (pintype "passive"))
    )
    (net (code "11") (name "/SW9") (class "Default")
      (node (ref "R71") (pin "1") (pinfunction "1_1") (pintype "passive"))
    )
    (net (code "12") (name "/SW10") (class "Default")
      (node (ref "R70") (pin "1") (pinfunction "1_1") (pintype "passive"))
    )
    (net (code "13") (name "/SW11") (class "Default")
      (node (ref "R69") (pin "1") (pinfunction "1_1") (pintype "passive"))
    )
    (net (code "14") (name "/SW12") (class "Default")
      (node (ref "R68") (pin "1") (pinfunction "1_1") (pintype "passive"))
    )
    (net (code "15") (name "/SW13") (class "Default")
      (node (ref "R67") (pin "1") (pinfunction "1_1") (pintype "passive"))
    )
    (net (code "16") (name "/SW14") (class "Default")
      (node (ref "R66") (pin "1") (pinfunction "1_1") (pintype "passive"))
    )
    (net (code "17") (name "/SW15") (class "Default")
      (node (ref "R65") (pin "1") (pinfunction "1_1") (pintype "passive"))
    )
    (net (code "18") (name "/SW16") (class "Default")
      (node (ref "R64") (pin "1") (pinfunction "1_1") (pintype "passive"))
    )
    (net (code "19") (name "/SW17") (class "Default")
      (node (ref "R63") (pin "1") (pinfunction "1_1") (pintype "passive"))
    )
    (net (code "20") (name "/SW18") (class "Default")
      (node (ref "R90") (pin "1") (pinfunction "1_1") (pintype "passive"))
    )
    (net (code "21") (name "/SW19") (class "Default")
      (node (ref "R91") (pin "1") (pinfunction "1_1") (pintype "passive"))
    )
    (net (code "22") (name "/SW20") (class "Default")
      (node (ref "R92") (pin "1") (pinfunction "1_1") (pintype "passive"))
    )
    (net (code "23") (name "/SW21") (class "Default")
      (node (ref "R93") (pin "1") (pinfunction "1_1") (pintype "passive"))
    )
    (net (code "24") (name "/SW22") (class "Default")
      (node (ref "R94") (pin "1") (pinfunction "1_1") (pintype "passive"))
    )
    (net (code "25") (name "/SW23") (class "Default")
      (node (ref "R95") (pin "1") (pinfunction "1_1") (pintype "passive"))
    )
    (net (code "26") (name "/SW24") (class "Default")
      (node (ref "R96") (pin "1") (pinfunction "1_1") (pintype "passive"))
    )
    (net (code "27") (name "/SW25") (class "Default")
      (node (ref "R97") (pin "1") (pinfunction "1_1") (pintype "passive"))
    )
    (net (code "28") (name "/SW26") (class "Default")
      (node (ref "R98") (pin "1") (pinfunction "1_1") (pintype "passive"))
    )
    (net (code "29") (name "/SW27") (class "Default")
      (node (ref "R116") (pin "1") (pinfunction "1_1") (pintype "passive"))
    )
    (net (code "30") (name "/SW28") (class "Default")
      (node (ref "R115") (pin "1") (pinfunction "1_1") (pintype "passive"))
    )
    (net (code "31") (name "/SW29") (class "Default")
      (node (ref "R114") (pin "1") (pinfunction "1_1") (pintype "passive"))
    )
    (net (code "32") (name "/SW30") (class "Default")
      (node (ref "R113") (pin "1") (pinfunction "1_1") (pintype "passive"))
    )
    (net (code "33") (name "/SW31") (class "Default")
      (node (ref "R112") (pin "1") (pinfunction "1_1") (pintype "passive"))
    )
    (net (code "34") (name "GND_AUX") (class "Default")
      (node (ref "Q11") (pin "2") (pinfunction "E_2") (pintype "passive"))
      (node (ref "Q12") (pin "2") (pinfunction "E_2") (pintype "passive"))
      (node (ref "Q13") (pin "2") (pinfunction "E_2") (pintype "passive"))
      (node (ref "Q14") (pin "2") (pinfunction "E_2") (pintype "passive"))
      (node (ref "Q15") (pin "2") (pinfunction "E_2") (pintype "passive"))
      (node (ref "Q16") (pin "2") (pinfunction "E_2") (pintype "passive"))
      (node (ref "Q17") (pin "2") (pinfunction "E_2") (pintype "passive"))
      (node (ref "Q18") (pin "2") (pinfunction "E_2") (pintype "passive"))
      (node (ref "Q19") (pin "2") (pinfunction "E_2") (pintype "passive"))
      (node (ref "Q29") (pin "2") (pinfunction "E_2") (pintype "passive"))
      (node (ref "Q30") (pin "2") (pinfunction "E_2") (pintype "passive"))
      (node (ref "Q31") (pin "2") (pinfunction "E_2") (pintype "passive"))
      (node (ref "Q32") (pin "2") (pinfunction "E_2") (pintype "passive"))
      (node (ref "Q33") (pin "2") (pinfunction "E_2") (pintype "passive"))
      (node (ref "Q34") (pin "2") (pinfunction "E_2") (pintype "passive"))
      (node (ref "Q35") (pin "2") (pinfunction "E_2") (pintype "passive"))
      (node (ref "Q36") (pin "2") (pinfunction "E_2") (pintype "passive"))
      (node (ref "Q37") (pin "2") (pinfunction "E_2") (pintype "passive"))
      (node (ref "Q47") (pin "2") (pinfunction "E_2") (pintype "passive"))
      (node (ref "Q48") (pin "2") (pinfunction "E_2") (pintype "passive"))
      (node (ref "Q49") (pin "2") (pinfunction "E_2") (pintype "passive"))
      (node (ref "Q50") (pin "2") (pinfunction "E_2") (pintype "passive"))
      (node (ref "Q51") (pin "2") (pinfunction "E_2") (pintype "passive"))
      (node (ref "Q52") (pin "2") (pinfunction "E_2") (pintype "passive"))
      (node (ref "Q53") (pin "2") (pinfunction "E_2") (pintype "passive"))
      (node (ref "Q54") (pin "2") (pinfunction "E_2") (pintype "passive"))
      (node (ref "Q55") (pin "2") (pinfunction "E_2") (pintype "passive"))
      (node (ref "Q63") (pin "2") (pinfunction "E_2") (pintype "passive"))
      (node (ref "Q64") (pin "2") (pinfunction "E_2") (pintype "passive"))
      (node (ref "Q65") (pin "2") (pinfunction "E_2") (pintype "passive"))
      (node (ref "Q66") (pin "2") (pinfunction "E_2") (pintype "passive"))
      (node (ref "Q67") (pin "2") (pinfunction "E_2") (pintype "passive"))
      (node (ref "R105") (pin "2") (pinfunction "2_2") (pintype "passive"))
      (node (ref "R111") (pin "2") (pinfunction "2_2") (pintype "passive"))
      (node (ref "R117") (pin "2") (pinfunction "2_2") (pintype "passive"))
      (node (ref "R118") (pin "2") (pinfunction "2_2") (pintype "passive"))
      (node (ref "R119") (pin "2") (pinfunction "2_2") (pintype "passive"))
      (node (ref "R120") (pin "2") (pinfunction "2_2") (pintype "passive"))
      (node (ref "R121") (pin "2") (pinfunction "2_2") (pintype "passive"))
      (node (ref "R122") (pin "2") (pinfunction "2_2") (pintype "passive"))
      (node (ref "R123") (pin "2") (pinfunction "2_2") (pintype "passive"))
      (node (ref "R124") (pin "2") (pinfunction "2_2") (pintype "passive"))
      (node (ref "R125") (pin "2") (pinfunction "2_2") (pintype "passive"))
      (node (ref "R126") (pin "2") (pinfunction "2_2") (pintype "passive"))
      (node (ref "R127") (pin "2") (pinfunction "2_2") (pintype "passive"))
      (node (ref "R128") (pin "2") (pinfunction "2_2") (pintype "passive"))
      (node (ref "R129") (pin "2") (pinfunction "2_2") (pintype "passive"))
      (node (ref "R130") (pin "2") (pinfunction "2_2") (pintype "passive"))
      (node (ref "R131") (pin "2") (pinfunction "2_2") (pintype "passive"))
      (node (ref "R132") (pin "2") (pinfunction "2_2") (pintype "passive"))
      (node (ref "R133") (pin "2") (pinfunction "2_2") (pintype "passive"))
      (node (ref "R134") (pin "2") (pinfunction "2_2") (pintype "passive"))
      (node (ref "R135") (pin "2") (pinfunction "2_2") (pintype "passive"))
      (node (ref "R136") (pin "2") (pinfunction "2_2") (pintype "passive"))
      (node (ref "R137") (pin "2") (pinfunction "2_2") (pintype "passive"))
      (node (ref "R138") (pin "2") (pinfunction "2_2") (pintype "passive"))
      (node (ref "R139") (pin "2") (pinfunction "2_2") (pintype "passive"))
      (node (ref "R140") (pin "2") (pinfunction "2_2") (pintype "passive"))
      (node (ref "R141") (pin "2") (pinfunction "2_2") (pintype "passive"))
      (node (ref "R142") (pin "2") (pinfunction "2_2") (pintype "passive"))
      (node (ref "R143") (pin "2") (pinfunction "2_2") (pintype "passive"))
      (node (ref "R144") (pin "2") (pinfunction "2_2") (pintype "passive"))
      (node (ref "R145") (pin "2") (pinfunction "2_2") (pintype "passive"))
      (node (ref "R146") (pin "2") (pinfunction "2_2") (pintype "passive"))
    )
    (net (code "35") (name "I_LD") (class "Default")
      (node (ref "Q10") (pin "2") (pintype "power_in"))
      (node (ref "Q2") (pin "2") (pintype "power_in"))
      (node (ref "Q20") (pin "2") (pintype "power_in"))
      (node (ref "Q21") (pin "2") (pintype "power_in"))
      (node (ref "Q22") (pin "2") (pintype "power_in"))
      (node (ref "Q23") (pin "2") (pintype "power_in"))
      (node (ref "Q24") (pin "2") (pintype "power_in"))
      (node (ref "Q25") (pin "2") (pintype "power_in"))
      (node (ref "Q26") (pin "2") (pintype "power_in"))
      (node (ref "Q27") (pin "2") (pintype "power_in"))
      (node (ref "Q28") (pin "2") (pintype "power_in"))
      (node (ref "Q3") (pin "2") (pintype "power_in"))
      (node (ref "Q38") (pin "2") (pintype "power_in"))
      (node (ref "Q39") (pin "2") (pintype "power_in"))
      (node (ref "Q4") (pin "2") (pintype "power_in"))
      (node (ref "Q40") (pin "2") (pintype "power_in"))
      (node (ref "Q41") (pin "2") (pintype "power_in"))
      (node (ref "Q42") (pin "2") (pintype "power_in"))
      (node (ref "Q43") (pin "2") (pintype "power_in"))
      (node (ref "Q44") (pin "2") (pintype "power_in"))
      (node (ref "Q45") (pin "2") (pintype "power_in"))
      (node (ref "Q46") (pin "2") (pintype "power_in"))
      (node (ref "Q5") (pin "2") (pintype "power_in"))
      (node (ref "Q57") (pin "2") (pintype "power_in"))
      (node (ref "Q58") (pin "2") (pintype "power_in"))
      (node (ref "Q59") (pin "2") (pintype "power_in"))
      (node (ref "Q6") (pin "2") (pintype "power_in"))
      (node (ref "Q60") (pin "2") (pintype "power_in"))
      (node (ref "Q61") (pin "2") (pintype "power_in"))
      (node (ref "Q7") (pin "2") (pintype "power_in"))
      (node (ref "Q8") (pin "2") (pintype "power_in"))
      (node (ref "Q9") (pin "2") (pintype "power_in"))
    )
    (net (code "36") (name "Net-(DIO1-A)") (class "Default")
      (node (ref "DIO1") (pin "1") (pinfunction "A_1") (pintype "passive"))
      (node (ref "LD1") (pin "3") (pinfunction "3_3") (pintype "passive"))
      (node (ref "Q2") (pin "3") (pintype "power_in"))
    )
    (net (code "37") (name "Net-(DIO2-A)") (class "Default")
      (node (ref "DIO2") (pin "1") (pinfunction "A_1") (pintype "passive"))
      (node (ref "LD2") (pin "3") (pinfunction "3_3") (pintype "passive"))
      (node (ref "Q3") (pin "3") (pintype "power_in"))
    )
    (net (code "38") (name "Net-(DIO3-A)") (class "Default")
      (node (ref "DIO3") (pin "1") (pinfunction "A_1") (pintype "passive"))
      (node (ref "LD3") (pin "3") (pinfunction "3_3") (pintype "passive"))
      (node (ref "Q4") (pin "3") (pintype "power_in"))
    )
    (net (code "39") (name "Net-(DIO4-A)") (class "Default")
      (node (ref "DIO4") (pin "1") (pinfunction "A_1") (pintype "passive"))
      (node (ref "LD4") (pin "3") (pinfunction "3_3") (pintype "passive"))
      (node (ref "Q5") (pin "3") (pintype "power_in"))
    )
    (net (code "40") (name "Net-(DIO5-A)") (class "Default")
      (node (ref "DIO5") (pin "1") (pinfunction "A_1") (pintype "passive"))
      (node (ref "LD5") (pin "3") (pinfunction "3_3") (pintype "passive"))
      (node (ref "Q6") (pin "3") (pintype "power_in"))
    )
    (net (code "41") (name "Net-(DIO6-A)") (class "Default")
      (node (ref "DIO6") (pin "1") (pinfunction "A_1") (pintype "passive"))
      (node (ref "LD6") (pin "3") (pinfunction "3_3") (pintype "passive"))
      (node (ref "Q7") (pin "3") (pintype "power_in"))
    )
    (net (code "42") (name "Net-(DIO7-A)") (class "Default")
      (node (ref "DIO7") (pin "1") (pinfunction "A_1") (pintype "passive"))
      (node (ref "LD7") (pin "3") (pinfunction "3_3") (pintype "passive"))
      (node (ref "Q8") (pin "3") (pintype "power_in"))
    )
    (net (code "43") (name "Net-(DIO8-A)") (class "Default")
      (node (ref "DIO8") (pin "1") (pinfunction "A_1") (pintype "passive"))
      (node (ref "LD8") (pin "3") (pinfunction "3_3") (pintype "passive"))
      (node (ref "Q9") (pin "3") (pintype "power_in"))
    )
    (net (code "44") (name "Net-(DIO9-A)") (class "Default")
      (node (ref "DIO9") (pin "1") (pinfunction "A_1") (pintype "passive"))
      (node (ref "LD9") (pin "3") (pinfunction "3_3") (pintype "passive"))
      (node (ref "Q10") (pin "3") (pintype "power_in"))
    )
    (net (code "45") (name "Net-(DIO10-A)") (class "Default")
      (node (ref "DIO10") (pin "1") (pinfunction "A_1") (pintype "passive"))
      (node (ref "LD18") (pin "3") (pinfunction "3_3") (pintype "passive"))
      (node (ref "Q20") (pin "3") (pintype "power_in"))
    )
    (net (code "46") (name "Net-(DIO11-A)") (class "Default")
      (node (ref "DIO11") (pin "1") (pinfunction "A_1") (pintype "passive"))
      (node (ref "LD17") (pin "3") (pinfunction "3_3") (pintype "passive"))
      (node (ref "Q21") (pin "3") (pintype "power_in"))
    )
    (net (code "47") (name "Net-(DIO12-A)") (class "Default")
      (node (ref "DIO12") (pin "1") (pinfunction "A_1") (pintype "passive"))
      (node (ref "LD16") (pin "3") (pinfunction "3_3") (pintype "passive"))
      (node (ref "Q22") (pin "3") (pintype "power_in"))
    )
    (net (code "48") (name "Net-(DIO13-A)") (class "Default")
      (node (ref "DIO13") (pin "1") (pinfunction "A_1") (pintype "passive"))
      (node (ref "LD15") (pin "3") (pinfunction "3_3") (pintype "passive"))
      (node (ref "Q23") (pin "3") (pintype "power_in"))
    )
    (net (code "49") (name "Net-(DIO14-A)") (class "Default")
      (node (ref "DIO14") (pin "1") (pinfunction "A_1") (pintype "passive"))
      (node (ref "LD14") (pin "3") (pinfunction "3_3") (pintype "passive"))
      (node (ref "Q24") (pin "3") (pintype "power_in"))
    )
    (net (code "50") (name "Net-(DIO15-A)") (class "Default")
      (node (ref "DIO15") (pin "1") (pinfunction "A_1") (pintype "passive"))
      (node (ref "LD13") (pin "3") (pinfunction "3_3") (pintype "passive"))
      (node (ref "Q25") (pin "3") (pintype "power_in"))
    )
    (net (code "51") (name "Net-(DIO16-A)") (class "Default")
      (node (ref "DIO16") (pin "1") (pinfunction "A_1") (pintype "passive"))
      (node (ref "LD12") (pin "3") (pinfunction "3_3") (pintype "passive"))
      (node (ref "Q26") (pin "3") (pintype "power_in"))
    )
    (net (code "52") (name "Net-(DIO17-A)") (class "Default")
      (node (ref "DIO17") (pin "1") (pinfunction "A_1") (pintype "passive"))
      (node (ref "LD11") (pin "3") (pinfunction "3_3") (pintype "passive"))
      (node (ref "Q27") (pin "3") (pintype "power_in"))
    )
    (net (code "53") (name "Net-(DIO18-A)") (class "Default")
      (node (ref "DIO18") (pin "1") (pinfunction "A_1") (pintype "passive"))
      (node (ref "LD10") (pin "3") (pinfunction "3_3") (pintype "passive"))
      (node (ref "Q28") (pin "3") (pintype "power_in"))
    )
    (net (code "54") (name "Net-(DIO19-A)") (class "Default")
      (node (ref "DIO19") (pin "1") (pinfunction "A_1") (pintype "passive"))
      (node (ref "LD19") (pin "3") (pinfunction "3_3") (pintype "passive"))
      (node (ref "Q38") (pin "3") (pintype "power_in"))
    )
    (net (code "55") (name "Net-(DIO20-A)") (class "Default")
      (node (ref "DIO20") (pin "1") (pinfunction "A_1") (pintype "passive"))
      (node (ref "LD20") (pin "3") (pinfunction "3_3") (pintype "passive"))
      (node (ref "Q39") (pin "3") (pintype "power_in"))
    )
    (net (code "56") (name "Net-(DIO21-A)") (class "Default")
      (node (ref "DIO21") (pin "1") (pinfunction "A_1") (pintype "passive"))
      (node (ref "LD21") (pin "3") (pinfunction "3_3") (pintype "passive"))
      (node (ref "Q40") (pin "3") (pintype "power_in"))
    )
    (net (code "57") (name "Net-(DIO22-A)") (class "Default")
      (node (ref "DIO22") (pin "1") (pinfunction "A_1") (pintype "passive"))
      (node (ref "LD22") (pin "3") (pinfunction "3_3") (pintype "passive"))
      (node (ref "Q41") (pin "3") (pintype "power_in"))
    )
    (net (code "58") (name "Net-(DIO23-A)") (class "Default")
      (node (ref "DIO23") (pin "1") (pinfunction "A_1") (pintype "passive"))
      (node (ref "LD23") (pin "3") (pinfunction "3_3") (pintype "passive"))
      (node (ref "Q42") (pin "3") (pintype "power_in"))
    )
    (net (code "59") (name "Net-(DIO24-A)") (class "Default")
      (node (ref "DIO24") (pin "1") (pinfunction "A_1") (pintype "passive"))
      (node (ref "LD24") (pin "3") (pinfunction "3_3") (pintype "passive"))
      (node (ref "Q43") (pin "3") (pintype "power_in"))
    )
    (net (code "60") (name "Net-(DIO25-A)") (class "Default")
      (node (ref "DIO25") (pin "1") (pinfunction "A_1") (pintype "passive"))
      (node (ref "LD25") (pin "3") (pinfunction "3_3") (pintype "passive"))
      (node (ref "Q44") (pin "3") (pintype "power_in"))
    )
    (net (code "61") (name "Net-(DIO26-A)") (class "Default")
      (node (ref "DIO26") (pin "1") (pinfunction "A_1") (pintype "passive"))
      (node (ref "LD26") (pin "3") (pinfunction "3_3") (pintype "passive"))
      (node (ref "Q45") (pin "3") (pintype "power_in"))
    )
    (net (code "62") (name "Net-(DIO27-A)") (class "Default")
      (node (ref "DIO27") (pin "1") (pinfunction "A_1") (pintype "passive"))
      (node (ref "LD27") (pin "3") (pinfunction "3_3") (pintype "passive"))
      (node (ref "Q46") (pin "3") (pintype "power_in"))
    )
    (net (code "63") (name "Net-(DIO28-A)") (class "Default")
      (node (ref "DIO28") (pin "1") (pinfunction "A_1") (pintype "passive"))
      (node (ref "LD32") (pin "3") (pinfunction "3_3") (pintype "passive"))
      (node (ref "Q57") (pin "3") (pintype "power_in"))
    )
    (net (code "64") (name "Net-(DIO29-A)") (class "Default")
      (node (ref "DIO29") (pin "1") (pinfunction "A_1") (pintype "passive"))
      (node (ref "LD31") (pin "3") (pinfunction "3_3") (pintype "passive"))
      (node (ref "Q58") (pin "3") (pintype "power_in"))
    )
    (net (code "65") (name "Net-(DIO30-A)") (class "Default")
      (node (ref "DIO30") (pin "1") (pinfunction "A_1") (pintype "passive"))
      (node (ref "LD30") (pin "3") (pinfunction "3_3") (pintype "passive"))
      (node (ref "Q59") (pin "3") (pintype "power_in"))
    )
    (net (code "66") (name "Net-(DIO31-A)") (class "Default")
      (node (ref "DIO31") (pin "1") (pinfunction "A_1") (pintype "passive"))
      (node (ref "LD29") (pin "3") (pinfunction "3_3") (pintype "passive"))
      (node (ref "Q60") (pin "3") (pintype "power_in"))
    )
    (net (code "67") (name "Net-(DIO32-A)") (class "Default")
      (node (ref "DIO32") (pin "1") (pinfunction "A_1") (pintype "passive"))
      (node (ref "LD28") (pin "3") (pinfunction "3_3") (pintype "passive"))
      (node (ref "Q61") (pin "3") (pintype "power_in"))
    )
    (net (code "68") (name "Net-(Q2-Pad1)") (class "Default")
      (node (ref "Q2") (pin "1") (pintype "power_in"))
      (node (ref "R18") (pin "2") (pinfunction "2_2") (pintype "passive"))
      (node (ref "R27") (pin "2") (pinfunction "2_2") (pintype "passive"))
    )
    (net (code "69") (name "Net-(Q3-Pad1)") (class "Default")
      (node (ref "Q3") (pin "1") (pintype "power_in"))
      (node (ref "R19") (pin "2") (pinfunction "2_2") (pintype "passive"))
      (node (ref "R28") (pin "2") (pinfunction "2_2") (pintype "passive"))
    )
    (net (code "70") (name "Net-(Q4-Pad1)") (class "Default")
      (node (ref "Q4") (pin "1") (pintype "power_in"))
      (node (ref "R20") (pin "2") (pinfunction "2_2") (pintype "passive"))
      (node (ref "R29") (pin "2") (pinfunction "2_2") (pintype "passive"))
    )
    (net (code "71") (name "Net-(Q5-Pad1)") (class "Default")
      (node (ref "Q5") (pin "1") (pintype "power_in"))
      (node (ref "R21") (pin "2") (pinfunction "2_2") (pintype "passive"))
      (node (ref "R30") (pin "2") (pinfunction "2_2") (pintype "passive"))
    )
    (net (code "72") (name "Net-(Q6-Pad1)") (class "Default")
      (node (ref "Q6") (pin "1") (pintype "power_in"))
      (node (ref "R22") (pin "2") (pinfunction "2_2") (pintype "passive"))
      (node (ref "R31") (pin "2") (pinfunction "2_2") (pintype "passive"))
    )
    (net (code "73") (name "Net-(Q7-Pad1)") (class "Default")
      (node (ref "Q7") (pin "1") (pintype "power_in"))
      (node (ref "R23") (pin "2") (pinfunction "2_2") (pintype "passive"))
      (node (ref "R32") (pin "2") (pinfunction "2_2") (pintype "passive"))
    )
    (net (code "74") (name "Net-(Q8-Pad1)") (class "Default")
      (node (ref "Q8") (pin "1") (pintype "power_in"))
      (node (ref "R24") (pin "2") (pinfunction "2_2") (pintype "passive"))
      (node (ref "R33") (pin "2") (pinfunction "2_2") (pintype "passive"))
    )
    (net (code "75") (name "Net-(Q9-Pad1)") (class "Default")
      (node (ref "Q9") (pin "1") (pintype "power_in"))
      (node (ref "R25") (pin "2") (pinfunction "2_2") (pintype "passive"))
      (node (ref "R34") (pin "2") (pinfunction "2_2") (pintype "passive"))
    )
    (net (code "76") (name "Net-(Q10-Pad1)") (class "Default")
      (node (ref "Q10") (pin "1") (pintype "power_in"))
      (node (ref "R26") (pin "2") (pinfunction "2_2") (pintype "passive"))
      (node (ref "R35") (pin "2") (pinfunction "2_2") (pintype "passive"))
    )
    (net (code "77") (name "Net-(Q11-B)") (class "Default")
      (node (ref "Q11") (pin "1") (pinfunction "B_1") (pintype "passive"))
      (node (ref "R105") (pin "1") (pinfunction "1_1") (pintype "passive"))
      (node (ref "R36") (pin "2") (pinfunction "2_2") (pintype "passive"))
    )
    (net (code "78") (name "Net-(Q11-C)") (class "Default")
      (node (ref "Q11") (pin "3") (pinfunction "C_3") (pintype "passive"))
      (node (ref "R27") (pin "1") (pinfunction "1_1") (pintype "passive"))
    )
    (net (code "79") (name "Net-(Q12-B)") (class "Default")
      (node (ref "Q12") (pin "1") (pinfunction "B_1") (pintype "passive"))
      (node (ref "R111") (pin "1") (pinfunction "1_1") (pintype "passive"))
      (node (ref "R37") (pin "2") (pinfunction "2_2") (pintype "passive"))
    )
    (net (code "80") (name "Net-(Q12-C)") (class "Default")
      (node (ref "Q12") (pin "3") (pinfunction "C_3") (pintype "passive"))
      (node (ref "R28") (pin "1") (pinfunction "1_1") (pintype "passive"))
    )
    (net (code "81") (name "Net-(Q13-B)") (class "Default")
      (node (ref "Q13") (pin "1") (pinfunction "B_1") (pintype "passive"))
      (node (ref "R117") (pin "1") (pinfunction "1_1") (pintype "passive"))
      (node (ref "R38") (pin "2") (pinfunction "2_2") (pintype "passive"))
    )
    (net (code "82") (name "Net-(Q13-C)") (class "Default")
      (node (ref "Q13") (pin "3") (pinfunction "C_3") (pintype "passive"))
      (node (ref "R29") (pin "1") (pinfunction "1_1") (pintype "passive"))
    )
    (net (code "83") (name "Net-(Q14-B)") (class "Default")
      (node (ref "Q14") (pin "1") (pinfunction "B_1") (pintype "passive"))
      (node (ref "R118") (pin "1") (pinfunction "1_1") (pintype "passive"))
      (node (ref "R39") (pin "2") (pinfunction "2_2") (pintype "passive"))
    )
    (net (code "84") (name "Net-(Q14-C)") (class "Default")
      (node (ref "Q14") (pin "3") (pinfunction "C_3") (pintype "passive"))
      (node (ref "R30") (pin "1") (pinfunction "1_1") (pintype "passive"))
    )
    (net (code "85") (name "Net-(Q15-B)") (class "Default")
      (node (ref "Q15") (pin "1") (pinfunction "B_1") (pintype "passive"))
      (node (ref "R119") (pin "1") (pinfunction "1_1") (pintype "passive"))
      (node (ref "R40") (pin "2") (pinfunction "2_2") (pintype "passive"))
    )
    (net (code "86") (name "Net-(Q15-C)") (class "Default")
      (node (ref "Q15") (pin "3") (pinfunction "C_3") (pintype "passive"))
      (node (ref "R31") (pin "1") (pinfunction "1_1") (pintype "passive"))
    )
    (net (code "87") (name "Net-(Q16-B)") (class "Default")
      (node (ref "Q16") (pin "1") (pinfunction "B_1") (pintype "passive"))
      (node (ref "R120") (pin "1") (pinfunction "1_1") (pintype "passive"))
      (node (ref "R41") (pin "2") (pinfunction "2_2") (pintype "passive"))
    )
    (net (code "88") (name "Net-(Q16-C)") (class "Default")
      (node (ref "Q16") (pin "3") (pinfunction "C_3") (pintype "passive"))
      (node (ref "R32") (pin "1") (pinfunction "1_1") (pintype "passive"))
    )
    (net (code "89") (name "Net-(Q17-B)") (class "Default")
      (node (ref "Q17") (pin "1") (pinfunction "B_1") (pintype "passive"))
      (node (ref "R121") (pin "1") (pinfunction "1_1") (pintype "passive"))
      (node (ref "R42") (pin "2") (pinfunction "2_2") (pintype "passive"))
    )
    (net (code "90") (name "Net-(Q17-C)") (class "Default")
      (node (ref "Q17") (pin "3") (pinfunction "C_3") (pintype "passive"))
      (node (ref "R33") (pin "1") (pinfunction "1_1") (pintype "passive"))
    )
    (net (code "91") (name "Net-(Q18-B)") (class "Default")
      (node (ref "Q18") (pin "1") (pinfunction "B_1") (pintype "passive"))
      (node (ref "R122") (pin "1") (pinfunction "1_1") (pintype "passive"))
      (node (ref "R43") (pin "2") (pinfunction "2_2") (pintype "passive"))
    )
    (net (code "92") (name "Net-(Q18-C)") (class "Default")
      (node (ref "Q18") (pin "3") (pinfunction "C_3") (pintype "passive"))
      (node (ref "R34") (pin "1") (pinfunction "1_1") (pintype "passive"))
    )
    (net (code "93") (name "Net-(Q19-B)") (class "Default")
      (node (ref "Q19") (pin "1") (pinfunction "B_1") (pintype "passive"))
      (node (ref "R123") (pin "1") (pinfunction "1_1") (pintype "passive"))
      (node (ref "R44") (pin "2") (pinfunction "2_2") (pintype "passive"))
    )
    (net (code "94") (name "Net-(Q19-C)") (class "Default")
      (node (ref "Q19") (pin "3") (pinfunction "C_3") (pintype "passive"))
      (node (ref "R35") (pin "1") (pinfunction "1_1") (pintype "passive"))
    )
    (net (code "95") (name "Net-(Q20-Pad1)") (class "Default")
      (node (ref "Q20") (pin "1") (pintype "power_in"))
      (node (ref "R45") (pin "2") (pinfunction "2_2") (pintype "passive"))
      (node (ref "R54") (pin "2") (pinfunction "2_2") (pintype "passive"))
    )
    (net (code "96") (name "Net-(Q21-Pad1)") (class "Default")
      (node (ref "Q21") (pin "1") (pintype "power_in"))
      (node (ref "R46") (pin "2") (pinfunction "2_2") (pintype "passive"))
      (node (ref "R55") (pin "2") (pinfunction "2_2") (pintype "passive"))
    )
    (net (code "97") (name "Net-(Q22-Pad1)") (class "Default")
      (node (ref "Q22") (pin "1") (pintype "power_in"))
      (node (ref "R47") (pin "2") (pinfunction "2_2") (pintype "passive"))
      (node (ref "R56") (pin "2") (pinfunction "2_2") (pintype "passive"))
    )
    (net (code "98") (name "Net-(Q23-Pad1)") (class "Default")
      (node (ref "Q23") (pin "1") (pintype "power_in"))
      (node (ref "R48") (pin "2") (pinfunction "2_2") (pintype "passive"))
      (node (ref "R57") (pin "2") (pinfunction "2_2") (pintype "passive"))
    )
    (net (code "99") (name "Net-(Q24-Pad1)") (class "Default")
      (node (ref "Q24") (pin "1") (pintype "power_in"))
      (node (ref "R49") (pin "2") (pinfunction "2_2") (pintype "passive"))
      (node (ref "R58") (pin "2") (pinfunction "2_2") (pintype "passive"))
    )
    (net (code "100") (name "Net-(Q25-Pad1)") (class "Default")
      (node (ref "Q25") (pin "1") (pintype "power_in"))
      (node (ref "R50") (pin "2") (pinfunction "2_2") (pintype "passive"))
      (node (ref "R59") (pin "2") (pinfunction "2_2") (pintype "passive"))
    )
    (net (code "101") (name "Net-(Q26-Pad1)") (class "Default")
      (node (ref "Q26") (pin "1") (pintype "power_in"))
      (node (ref "R51") (pin "2") (pinfunction "2_2") (pintype "passive"))
      (node (ref "R60") (pin "2") (pinfunction "2_2") (pintype "passive"))
    )
    (net (code "102") (name "Net-(Q27-Pad1)") (class "Default")
      (node (ref "Q27") (pin "1") (pintype "power_in"))
      (node (ref "R52") (pin "2") (pinfunction "2_2") (pintype "passive"))
      (node (ref "R61") (pin "2") (pinfunction "2_2") (pintype "passive"))
    )
    (net (code "103") (name "Net-(Q28-Pad1)") (class "Default")
      (node (ref "Q28") (pin "1") (pintype "power_in"))
      (node (ref "R53") (pin "2") (pinfunction "2_2") (pintype "passive"))
      (node (ref "R62") (pin "2") (pinfunction "2_2") (pintype "passive"))
    )
    (net (code "104") (name "Net-(Q29-B)") (class "Default")
      (node (ref "Q29") (pin "1") (pinfunction "B_1") (pintype "passive"))
      (node (ref "R124") (pin "1") (pinfunction "1_1") (pintype "passive"))
      (node (ref "R63") (pin "2") (pinfunction "2_2") (pintype "passive"))
    )
    (net (code "105") (name "Net-(Q29-C)") (class "Default")
      (node (ref "Q29") (pin "3") (pinfunction "C_3") (pintype "passive"))
      (node (ref "R54") (pin "1") (pinfunction "1_1") (pintype "passive"))
    )
    (net (code "106") (name "Net-(Q30-B)") (class "Default")
      (node (ref "Q30") (pin "1") (pinfunction "B_1") (pintype "passive"))
      (node (ref "R125") (pin "1") (pinfunction "1_1") (pintype "passive"))
      (node (ref "R64") (pin "2") (pinfunction "2_2") (pintype "passive"))
    )
    (net (code "107") (name "Net-(Q30-C)") (class "Default")
      (node (ref "Q30") (pin "3") (pinfunction "C_3") (pintype "passive"))
      (node (ref "R55") (pin "1") (pinfunction "1_1") (pintype "passive"))
    )
    (net (code "108") (name "Net-(Q31-B)") (class "Default")
      (node (ref "Q31") (pin "1") (pinfunction "B_1") (pintype "passive"))
      (node (ref "R126") (pin "1") (pinfunction "1_1") (pintype "passive"))
      (node (ref "R65") (pin "2") (pinfunction "2_2") (pintype "passive"))
    )
    (net (code "109") (name "Net-(Q31-C)") (class "Default")
      (node (ref "Q31") (pin "3") (pinfunction "C_3") (pintype "passive"))
      (node (ref "R56") (pin "1") (pinfunction "1_1") (pintype "passive"))
    )
    (net (code "110") (name "Net-(Q32-B)") (class "Default")
      (node (ref "Q32") (pin "1") (pinfunction "B_1") (pintype "passive"))
      (node (ref "R127") (pin "1") (pinfunction "1_1") (pintype "passive"))
      (node (ref "R66") (pin "2") (pinfunction "2_2") (pintype "passive"))
    )
    (net (code "111") (name "Net-(Q32-C)") (class "Default")
      (node (ref "Q32") (pin "3") (pinfunction "C_3") (pintype "passive"))
      (node (ref "R57") (pin "1") (pinfunction "1_1") (pintype "passive"))
    )
    (net (code "112") (name "Net-(Q33-B)") (class "Default")
      (node (ref "Q33") (pin "1") (pinfunction "B_1") (pintype "passive"))
      (node (ref "R128") (pin "1") (pinfunction "1_1") (pintype "passive"))
      (node (ref "R67") (pin "2") (pinfunction "2_2") (pintype "passive"))
    )
    (net (code "113") (name "Net-(Q33-C)") (class "Default")
      (node (ref "Q33") (pin "3") (pinfunction "C_3") (pintype "passive"))
      (node (ref "R58") (pin "1") (pinfunction "1_1") (pintype "passive"))
    )
    (net (code "114") (name "Net-(Q34-B)") (class "Default")
      (node (ref "Q34") (pin "1") (pinfunction "B_1") (pintype "passive"))
      (node (ref "R129") (pin "1") (pinfunction "1_1") (pintype "passive"))
      (node (ref "R68") (pin "2") (pinfunction "2_2") (pintype "passive"))
    )
    (net (code "115") (name "Net-(Q34-C)") (class "Default")
      (node (ref "Q34") (pin "3") (pinfunction "C_3") (pintype "passive"))
      (node (ref "R59") (pin "1") (pinfunction "1_1") (pintype "passive"))
    )
    (net (code "116") (name "Net-(Q35-B)") (class "Default")
      (node (ref "Q35") (pin "1") (pinfunction "B_1") (pintype "passive"))
      (node (ref "R130") (pin "1") (pinfunction "1_1") (pintype "passive"))
      (node (ref "R69") (pin "2") (pinfunction "2_2") (pintype "passive"))
    )
    (net (code "117") (name "Net-(Q35-C)") (class "Default")
      (node (ref "Q35") (pin "3") (pinfunction "C_3") (pintype "passive"))
      (node (ref "R60") (pin "1") (pinfunction "1_1") (pintype "passive"))
    )
    (net (code "118") (name "Net-(Q36-B)") (class "Default")
      (node (ref "Q36") (pin "1") (pinfunction "B_1") (pintype "passive"))
      (node (ref "R131") (pin "1") (pinfunction "1_1") (pintype "passive"))
      (node (ref "R70") (pin "2") (pinfunction "2_2") (pintype "passive"))
    )
    (net (code "119") (name "Net-(Q36-C)") (class "Default")
      (node (ref "Q36") (pin "3") (pinfunction "C_3") (pintype "passive"))
      (node (ref "R61") (pin "1") (pinfunction "1_1") (pintype "passive"))
    )
    (net (code "120") (name "Net-(Q37-B)") (class "Default")
      (node (ref "Q37") (pin "1") (pinfunction "B_1") (pintype "passive"))
      (node (ref "R132") (pin "1") (pinfunction "1_1") (pintype "passive"))
      (node (ref "R71") (pin "2") (pinfunction "2_2") (pintype "passive"))
    )
    (net (code "121") (name "Net-(Q37-C)") (class "Default")
      (node (ref "Q37") (pin "3") (pinfunction "C_3") (pintype "passive"))
      (node (ref "R62") (pin "1") (pinfunction "1_1") (pintype "passive"))
    )
    (net (code "122") (name "Net-(Q38-Pad1)") (class "Default")
      (node (ref "Q38") (pin "1") (pintype "power_in"))
      (node (ref "R72") (pin "2") (pinfunction "2_2") (pintype "passive"))
      (node (ref "R81") (pin "2") (pinfunction "2_2") (pintype "passive"))
    )
    (net (code "123") (name "Net-(Q39-Pad1)") (class "Default")
      (node (ref "Q39") (pin "1") (pintype "power_in"))
      (node (ref "R73") (pin "2") (pinfunction "2_2") (pintype "passive"))
      (node (ref "R82") (pin "2") (pinfunction "2_2") (pintype "passive"))
    )
    (net (code "124") (name "Net-(Q40-Pad1)") (class "Default")
      (node (ref "Q40") (pin "1") (pintype "power_in"))
      (node (ref "R74") (pin "2") (pinfunction "2_2") (pintype "passive"))
      (node (ref "R83") (pin "2") (pinfunction "2_2") (pintype "passive"))
    )
    (net (code "125") (name "Net-(Q41-Pad1)") (class "Default")
      (node (ref "Q41") (pin "1") (pintype "power_in"))
      (node (ref "R75") (pin "2") (pinfunction "2_2") (pintype "passive"))
      (node (ref "R84") (pin "2") (pinfunction "2_2") (pintype "passive"))
    )
    (net (code "126") (name "Net-(Q42-Pad1)") (class "Default")
      (node (ref "Q42") (pin "1") (pintype "power_in"))
      (node (ref "R76") (pin "2") (pinfunction "2_2") (pintype "passive"))
      (node (ref "R85") (pin "2") (pinfunction "2_2") (pintype "passive"))
    )
    (net (code "127") (name "Net-(Q43-Pad1)") (class "Default")
      (node (ref "Q43") (pin "1") (pintype "power_in"))
      (node (ref "R77") (pin "2") (pinfunction "2_2") (pintype "passive"))
      (node (ref "R86") (pin "2") (pinfunction "2_2") (pintype "passive"))
    )
    (net (code "128") (name "Net-(Q44-Pad1)") (class "Default")
      (node (ref "Q44") (pin "1") (pintype "power_in"))
      (node (ref "R78") (pin "2") (pinfunction "2_2") (pintype "passive"))
      (node (ref "R87") (pin "2") (pinfunction "2_2") (pintype "passive"))
    )
    (net (code "129") (name "Net-(Q45-Pad1)") (class "Default")
      (node (ref "Q45") (pin "1") (pintype "power_in"))
      (node (ref "R79") (pin "2") (pinfunction "2_2") (pintype "passive"))
      (node (ref "R88") (pin "2") (pinfunction "2_2") (pintype "passive"))
    )
    (net (code "130") (name "Net-(Q46-Pad1)") (class "Default")
      (node (ref "Q46") (pin "1") (pintype "power_in"))
      (node (ref "R80") (pin "2") (pinfunction "2_2") (pintype "passive"))
      (node (ref "R89") (pin "2") (pinfunction "2_2") (pintype "passive"))
    )
    (net (code "131") (name "Net-(Q47-B)") (class "Default")
      (node (ref "Q47") (pin "1") (pinfunction "B_1") (pintype "passive"))
      (node (ref "R133") (pin "1") (pinfunction "1_1") (pintype "passive"))
      (node (ref "R90") (pin "2") (pinfunction "2_2") (pintype "passive"))
    )
    (net (code "132") (name "Net-(Q47-C)") (class "Default")
      (node (ref "Q47") (pin "3") (pinfunction "C_3") (pintype "passive"))
      (node (ref "R81") (pin "1") (pinfunction "1_1") (pintype "passive"))
    )
    (net (code "133") (name "Net-(Q48-B)") (class "Default")
      (node (ref "Q48") (pin "1") (pinfunction "B_1") (pintype "passive"))
      (node (ref "R134") (pin "1") (pinfunction "1_1") (pintype "passive"))
      (node (ref "R91") (pin "2") (pinfunction "2_2") (pintype "passive"))
    )
    (net (code "134") (name "Net-(Q48-C)") (class "Default")
      (node (ref "Q48") (pin "3") (pinfunction "C_3") (pintype "passive"))
      (node (ref "R82") (pin "1") (pinfunction "1_1") (pintype "passive"))
    )
    (net (code "135") (name "Net-(Q49-B)") (class "Default")
      (node (ref "Q49") (pin "1") (pinfunction "B_1") (pintype "passive"))
      (node (ref "R135") (pin "1") (pinfunction "1_1") (pintype "passive"))
      (node (ref "R92") (pin "2") (pinfunction "2_2") (pintype "passive"))
    )
    (net (code "136") (name "Net-(Q49-C)") (class "Default")
      (node (ref "Q49") (pin "3") (pinfunction "C_3") (pintype "passive"))
      (node (ref "R83") (pin "1") (pinfunction "1_1") (pintype "passive"))
    )
    (net (code "137") (name "Net-(Q50-B)") (class "Default")
      (node (ref "Q50") (pin "1") (pinfunction "B_1") (pintype "passive"))
      (node (ref "R136") (pin "1") (pinfunction "1_1") (pintype "passive"))
      (node (ref "R93") (pin "2") (pinfunction "2_2") (pintype "passive"))
    )
    (net (code "138") (name "Net-(Q50-C)") (class "Default")
      (node (ref "Q50") (pin "3") (pinfunction "C_3") (pintype "passive"))
      (node (ref "R84") (pin "1") (pinfunction "1_1") (pintype "passive"))
    )
    (net (code "139") (name "Net-(Q51-B)") (class "Default")
      (node (ref "Q51") (pin "1") (pinfunction "B_1") (pintype "passive"))
      (node (ref "R137") (pin "1") (pinfunction "1_1") (pintype "passive"))
      (node (ref "R94") (pin "2") (pinfunction "2_2") (pintype "passive"))
    )
    (net (code "140") (name "Net-(Q51-C)") (class "Default")
      (node (ref "Q51") (pin "3") (pinfunction "C_3") (pintype "passive"))
      (node (ref "R85") (pin "1") (pinfunction "1_1") (pintype "passive"))
    )
    (net (code "141") (name "Net-(Q52-B)") (class "Default")
      (node (ref "Q52") (pin "1") (pinfunction "B_1") (pintype "passive"))
      (node (ref "R138") (pin "1") (pinfunction "1_1") (pintype "passive"))
      (node (ref "R95") (pin "2") (pinfunction "2_2") (pintype "passive"))
    )
    (net (code "142") (name "Net-(Q52-C)") (class "Default")
      (node (ref "Q52") (pin "3") (pinfunction "C_3") (pintype "passive"))
      (node (ref "R86") (pin "1") (pinfunction "1_1") (pintype "passive"))
    )
    (net (code "143") (name "Net-(Q53-B)") (class "Default")
      (node (ref "Q53") (pin "1") (pinfunction "B_1") (pintype "passive"))
      (node (ref "R139") (pin "1") (pinfunction "1_1") (pintype "passive"))
      (node (ref "R96") (pin "2") (pinfunction "2_2") (pintype "passive"))
    )
    (net (code "144") (name "Net-(Q53-C)") (class "Default")
      (node (ref "Q53") (pin "3") (pinfunction "C_3") (pintype "passive"))
      (node (ref "R87") (pin "1") (pinfunction "1_1") (pintype "passive"))
    )
    (net (code "145") (name "Net-(Q54-B)") (class "Default")
      (node (ref "Q54") (pin "1") (pinfunction "B_1") (pintype "passive"))
      (node (ref "R140") (pin "1") (pinfunction "1_1") (pintype "passive"))
      (node (ref "R97") (pin "2") (pinfunction "2_2") (pintype "passive"))
    )
    (net (code "146") (name "Net-(Q54-C)") (class "Default")
      (node (ref "Q54") (pin "3") (pinfunction "C_3") (pintype "passive"))
      (node (ref "R88") (pin "1") (pinfunction "1_1") (pintype "passive"))
    )
    (net (code "147") (name "Net-(Q55-B)") (class "Default")
      (node (ref "Q55") (pin "1") (pinfunction "B_1") (pintype "passive"))
      (node (ref "R141") (pin "1") (pinfunction "1_1") (pintype "passive"))
      (node (ref "R98") (pin "2") (pinfunction "2_2") (pintype "passive"))
    )
    (net (code "148") (name "Net-(Q55-C)") (class "Default")
      (node (ref "Q55") (pin "3") (pinfunction "C_3") (pintype "passive"))
      (node (ref "R89") (pin "1") (pinfunction "1_1") (pintype "passive"))
    )
    (net (code "149") (name "Net-(Q57-Pad1)") (class "Default")
      (node (ref "Q57") (pin "1") (pintype "power_in"))
      (node (ref "R100") (pin "2") (pinfunction "2_2") (pintype "passive"))
      (node (ref "R106") (pin "2") (pinfunction "2_2") (pintype "passive"))
    )
    (net (code "150") (name "Net-(Q58-Pad1)") (class "Default")
      (node (ref "Q58") (pin "1") (pintype "power_in"))
      (node (ref "R101") (pin "2") (pinfunction "2_2") (pintype "passive"))
      (node (ref "R107") (pin "2") (pinfunction "2_2") (pintype "passive"))
    )
    (net (code "151") (name "Net-(Q59-Pad1)") (class "Default")
      (node (ref "Q59") (pin "1") (pintype "power_in"))
      (node (ref "R102") (pin "2") (pinfunction "2_2") (pintype "passive"))
      (node (ref "R108") (pin "2") (pinfunction "2_2") (pintype "passive"))
    )
    (net (code "152") (name "Net-(Q60-Pad1)") (class "Default")
      (node (ref "Q60") (pin "1") (pintype "power_in"))
      (node (ref "R103") (pin "2") (pinfunction "2_2") (pintype "passive"))
      (node (ref "R109") (pin "2") (pinfunction "2_2") (pintype "passive"))
    )
    (net (code "153") (name "Net-(Q61-Pad1)") (class "Default")
      (node (ref "Q61") (pin "1") (pintype "power_in"))
      (node (ref "R104") (pin "2") (pinfunction "2_2") (pintype "passive"))
      (node (ref "R110") (pin "2") (pinfunction "2_2") (pintype "passive"))
    )
    (net (code "154") (name "Net-(Q63-B)") (class "Default")
      (node (ref "Q63") (pin "1") (pinfunction "B_1") (pintype "passive"))
      (node (ref "R112") (pin "2") (pinfunction "2_2") (pintype "passive"))
      (node (ref "R142") (pin "1") (pinfunction "1_1") (pintype "passive"))
    )
    (net (code "155") (name "Net-(Q63-C)") (class "Default")
      (node (ref "Q63") (pin "3") (pinfunction "C_3") (pintype "passive"))
      (node (ref "R106") (pin "1") (pinfunction "1_1") (pintype "passive"))
    )
    (net (code "156") (name "Net-(Q64-B)") (class "Default")
      (node (ref "Q64") (pin "1") (pinfunction "B_1") (pintype "passive"))
      (node (ref "R113") (pin "2") (pinfunction "2_2") (pintype "passive"))
      (node (ref "R143") (pin "1") (pinfunction "1_1") (pintype "passive"))
    )
    (net (code "157") (name "Net-(Q64-C)") (class "Default")
      (node (ref "Q64") (pin "3") (pinfunction "C_3") (pintype "passive"))
      (node (ref "R107") (pin "1") (pinfunction "1_1") (pintype "passive"))
    )
    (net (code "158") (name "Net-(Q65-B)") (class "Default")
      (node (ref "Q65") (pin "1") (pinfunction "B_1") (pintype "passive"))
      (node (ref "R114") (pin "2") (pinfunction "2_2") (pintype "passive"))
      (node (ref "R144") (pin "1") (pinfunction "1_1") (pintype "passive"))
    )
    (net (code "159") (name "Net-(Q65-C)") (class "Default")
      (node (ref "Q65") (pin "3") (pinfunction "C_3") (pintype "passive"))
      (node (ref "R108") (pin "1") (pinfunction "1_1") (pintype "passive"))
    )
    (net (code "160") (name "Net-(Q66-B)") (class "Default")
      (node (ref "Q66") (pin "1") (pinfunction "B_1") (pintype "passive"))
      (node (ref "R115") (pin "2") (pinfunction "2_2") (pintype "passive"))
      (node (ref "R145") (pin "1") (pinfunction "1_1") (pintype "passive"))
    )
    (net (code "161") (name "Net-(Q66-C)") (class "Default")
      (node (ref "Q66") (pin "3") (pinfunction "C_3") (pintype "passive"))
      (node (ref "R109") (pin "1") (pinfunction "1_1") (pintype "passive"))
    )
    (net (code "162") (name "Net-(Q67-B)") (class "Default")
      (node (ref "Q67") (pin "1") (pinfunction "B_1") (pintype "passive"))
      (node (ref "R116") (pin "2") (pinfunction "2_2") (pintype "passive"))
      (node (ref "R146") (pin "1") (pinfunction "1_1") (pintype "passive"))
    )
    (net (code "163") (name "Net-(Q67-C)") (class "Default")
      (node (ref "Q67") (pin "3") (pinfunction "C_3") (pintype "passive"))
      (node (ref "R110") (pin "1") (pinfunction "1_1") (pintype "passive"))
    )
  )
)
